# slave_board.net
KiCad netlist of a schematic drawn in EAGLE
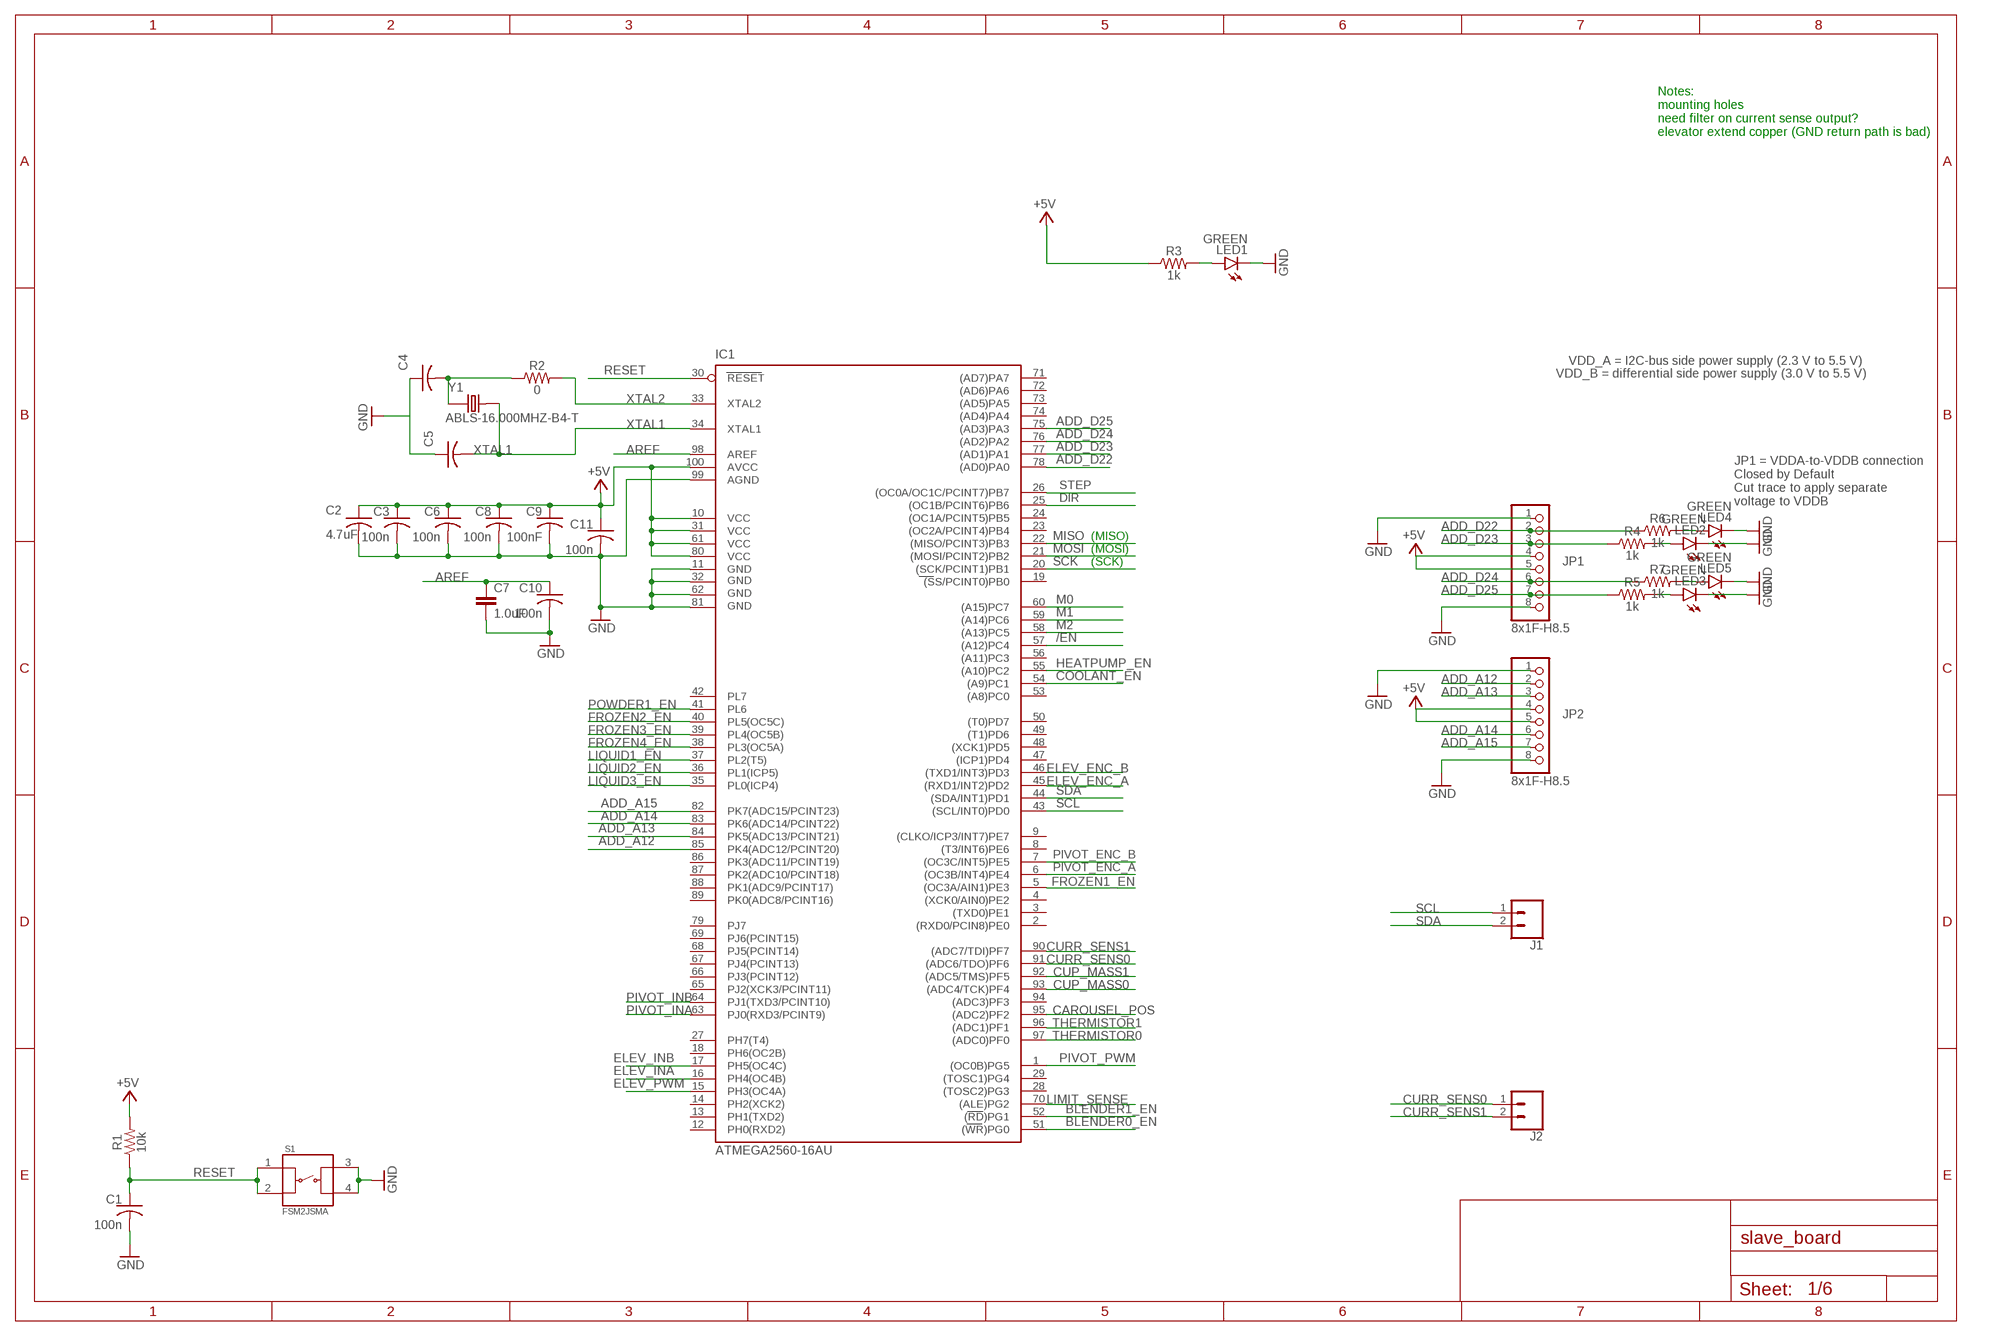
[diagram p0: schematic, sheet 1]
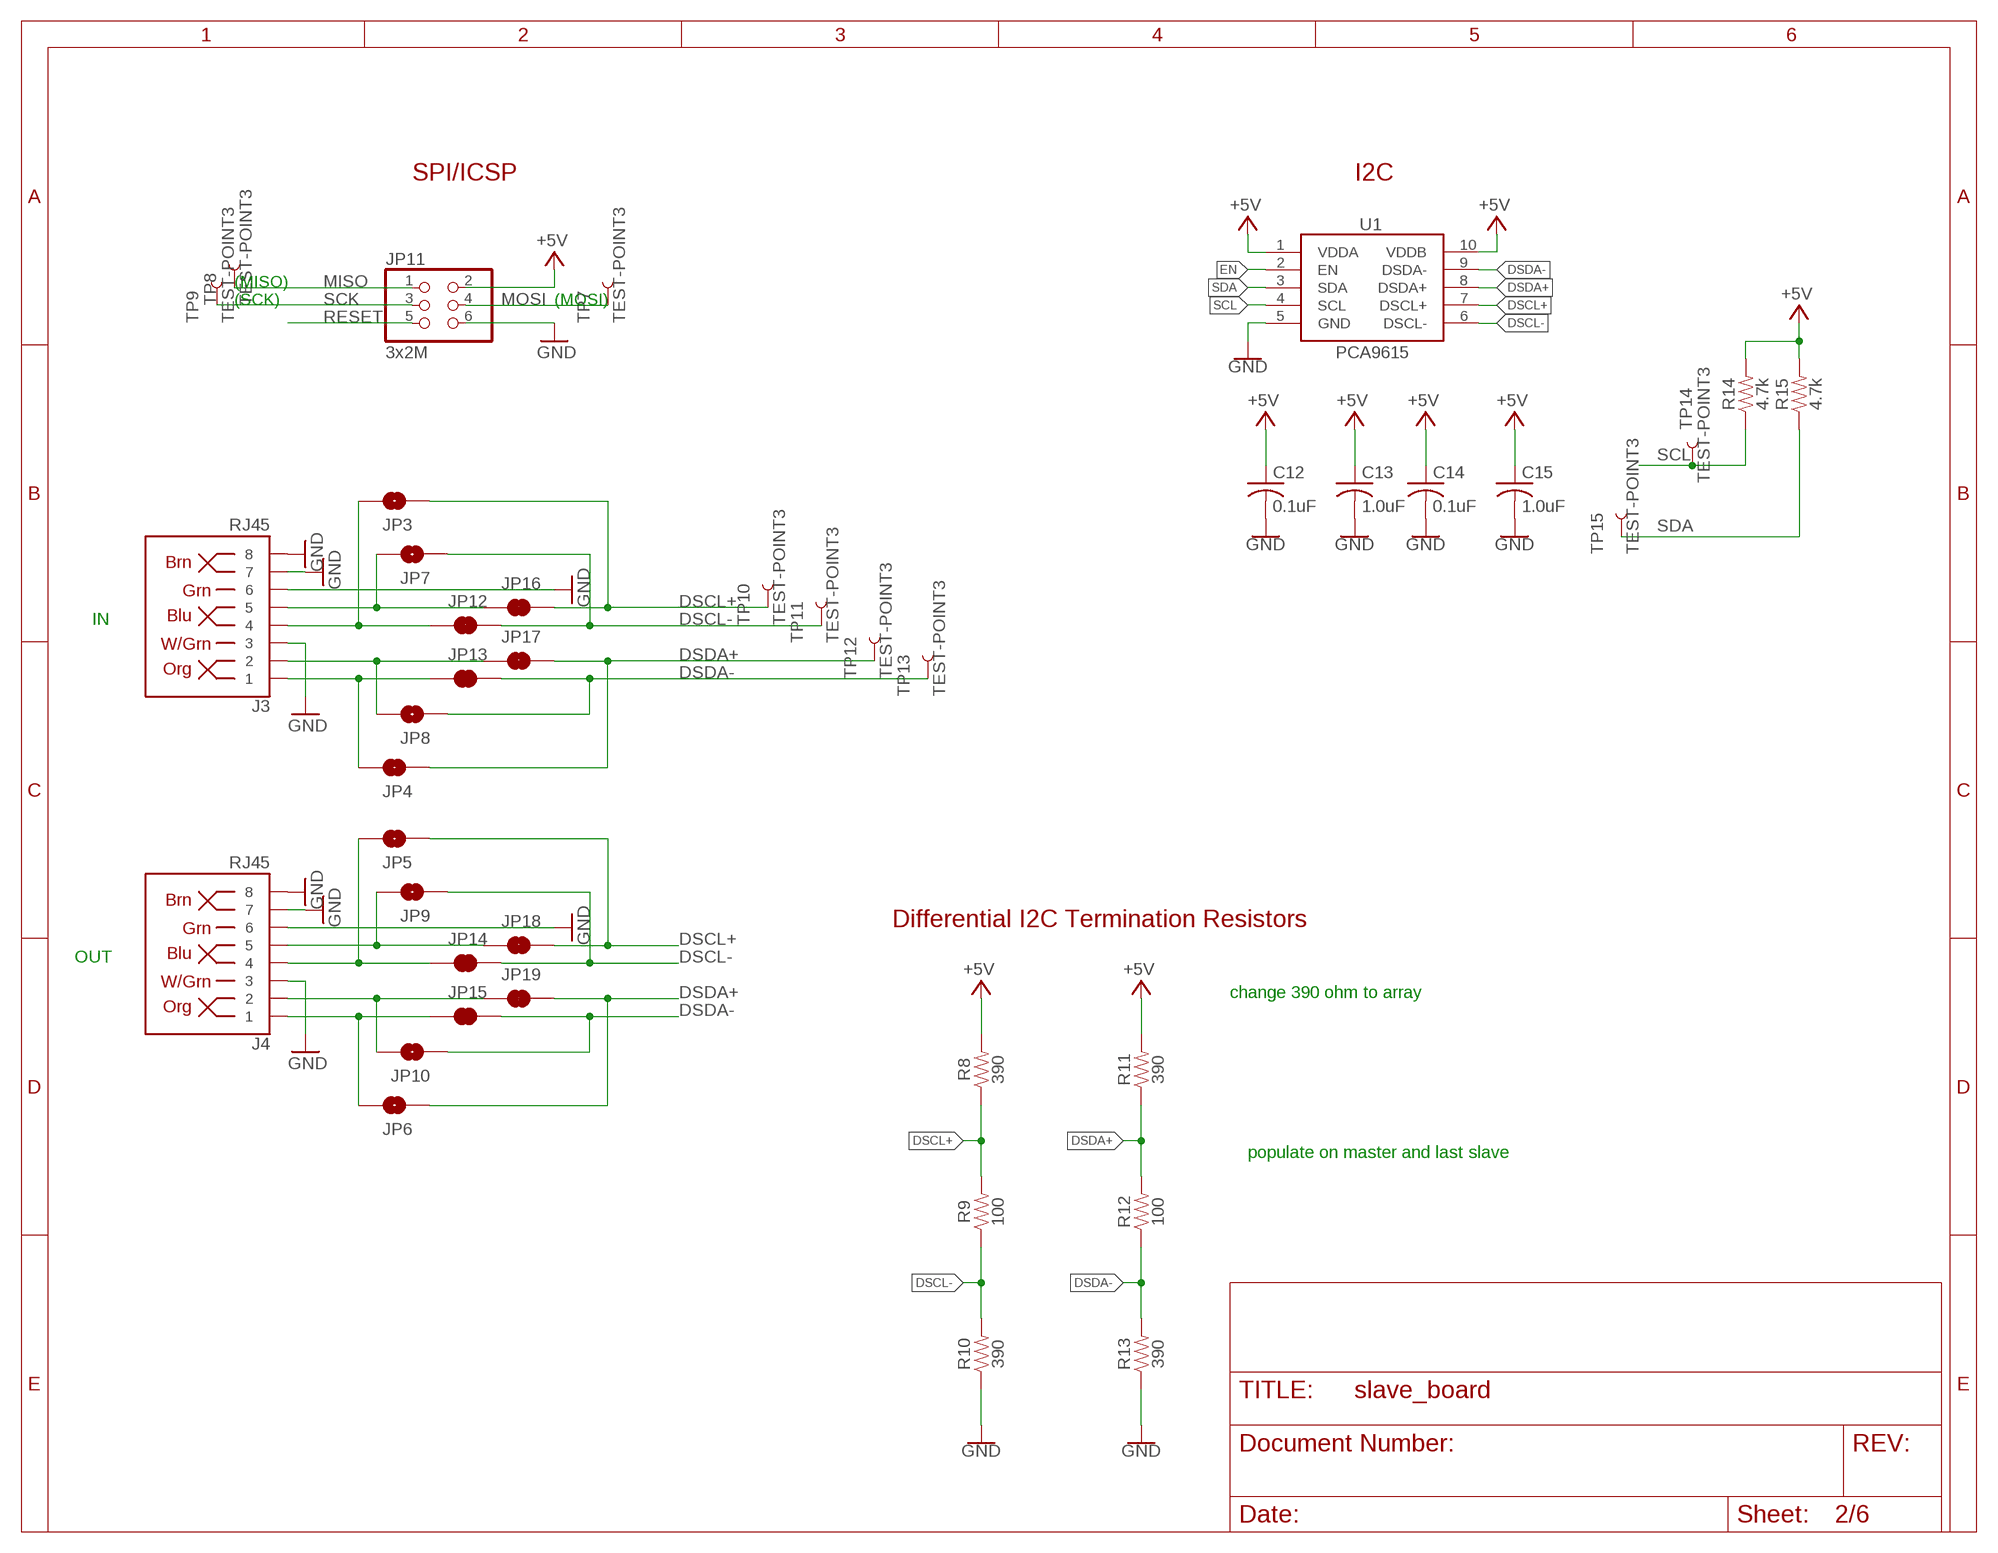
[diagram p1: schematic, sheet 2]
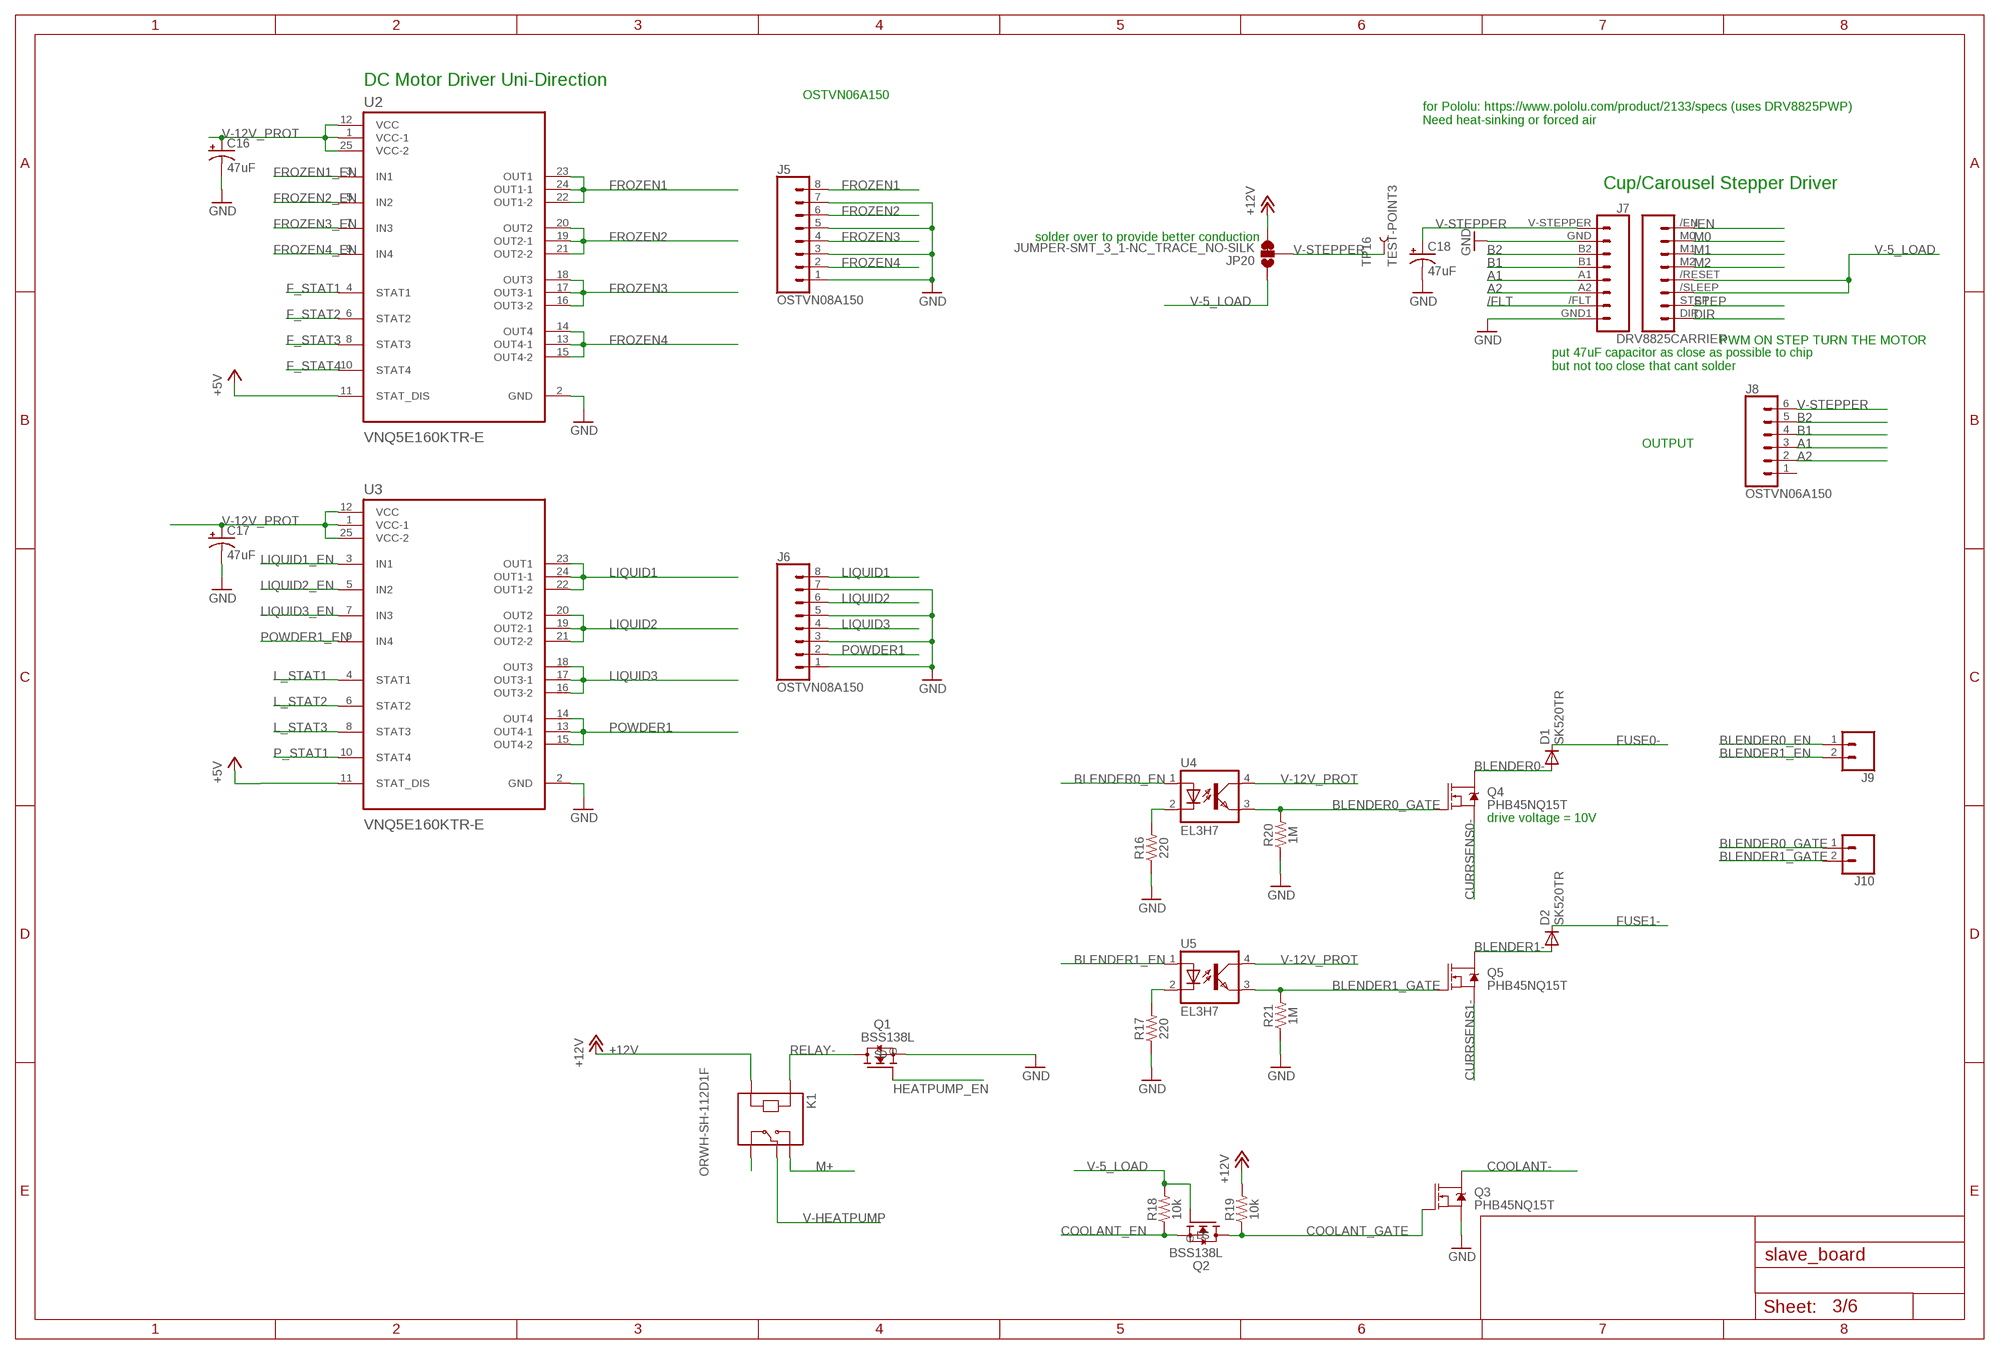
[diagram p2: schematic, sheet 3]
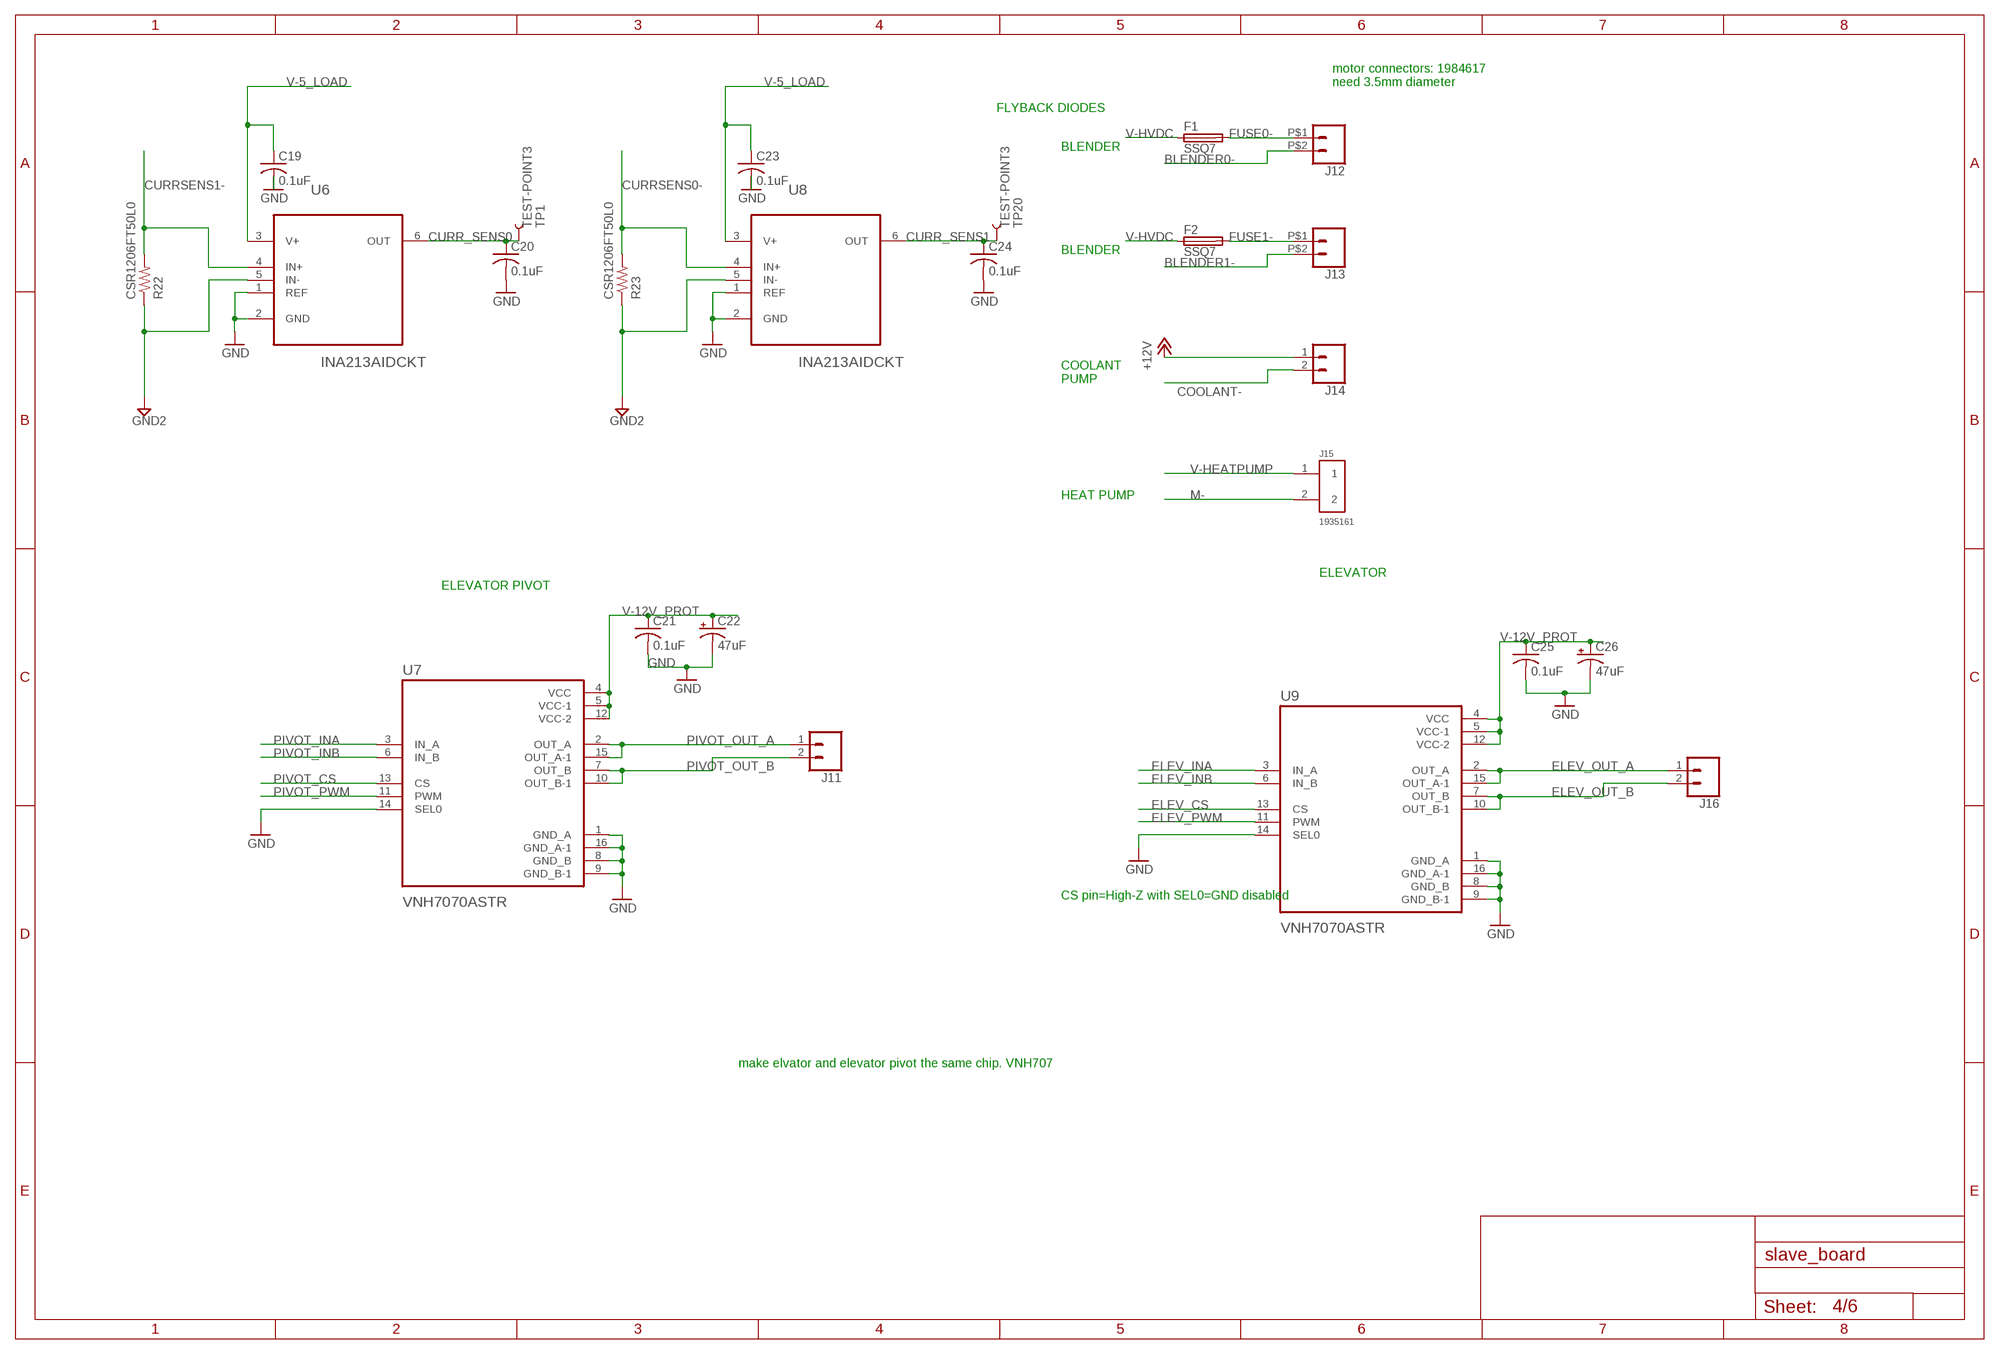
[diagram p3: schematic, sheet 4]
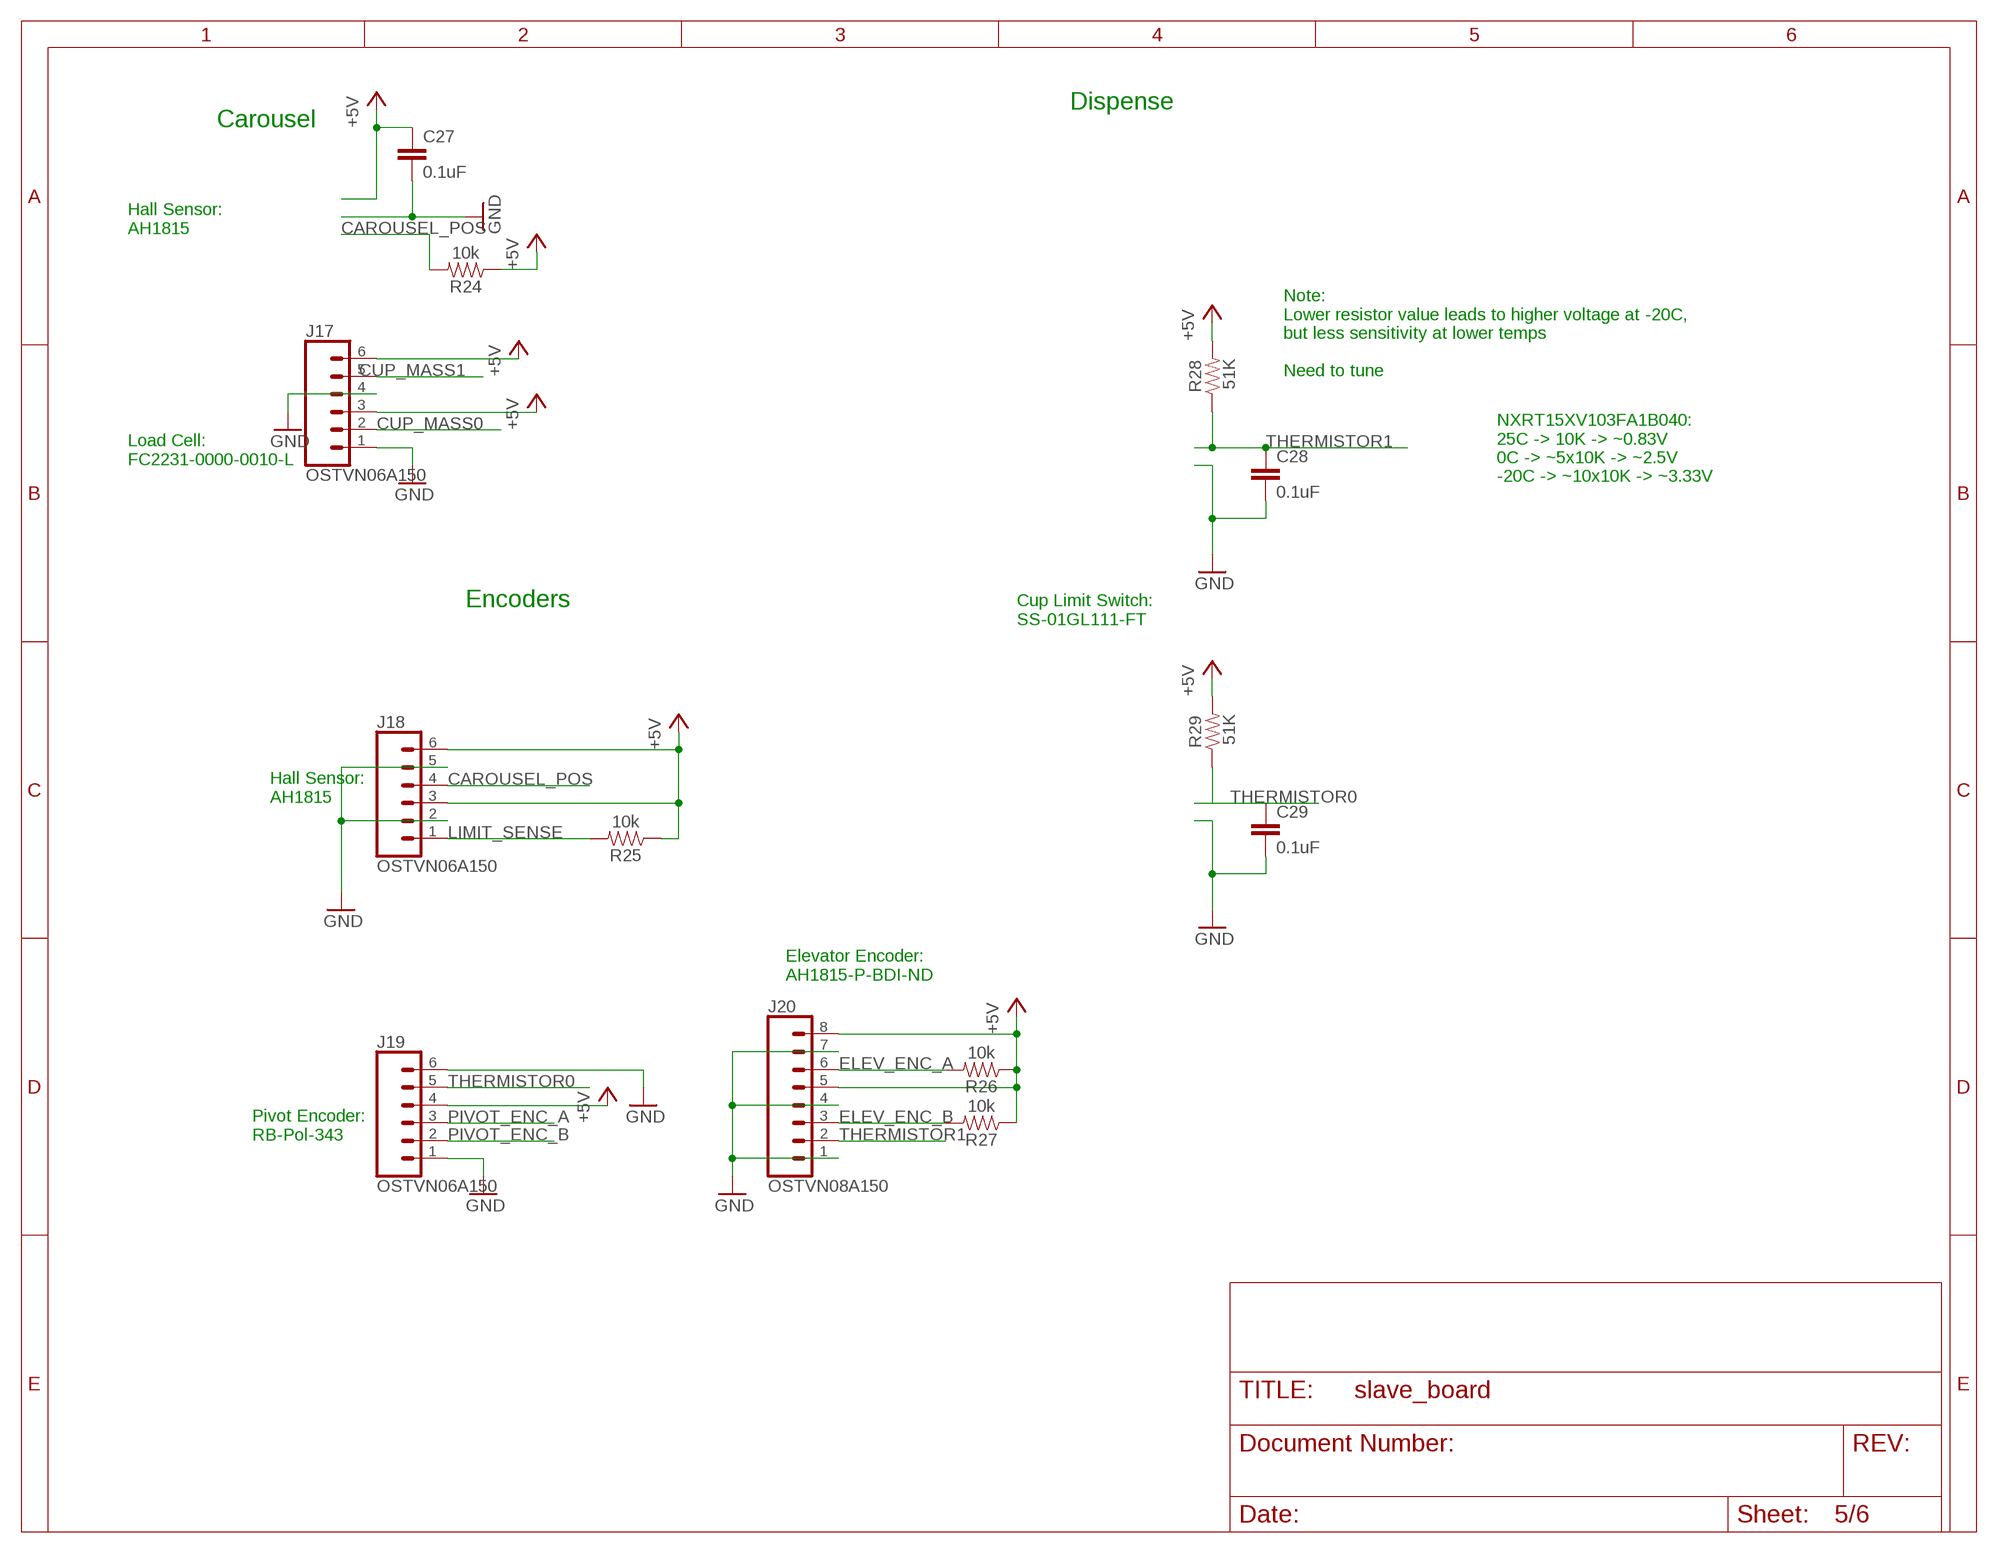
[diagram p4: schematic, sheet 5]
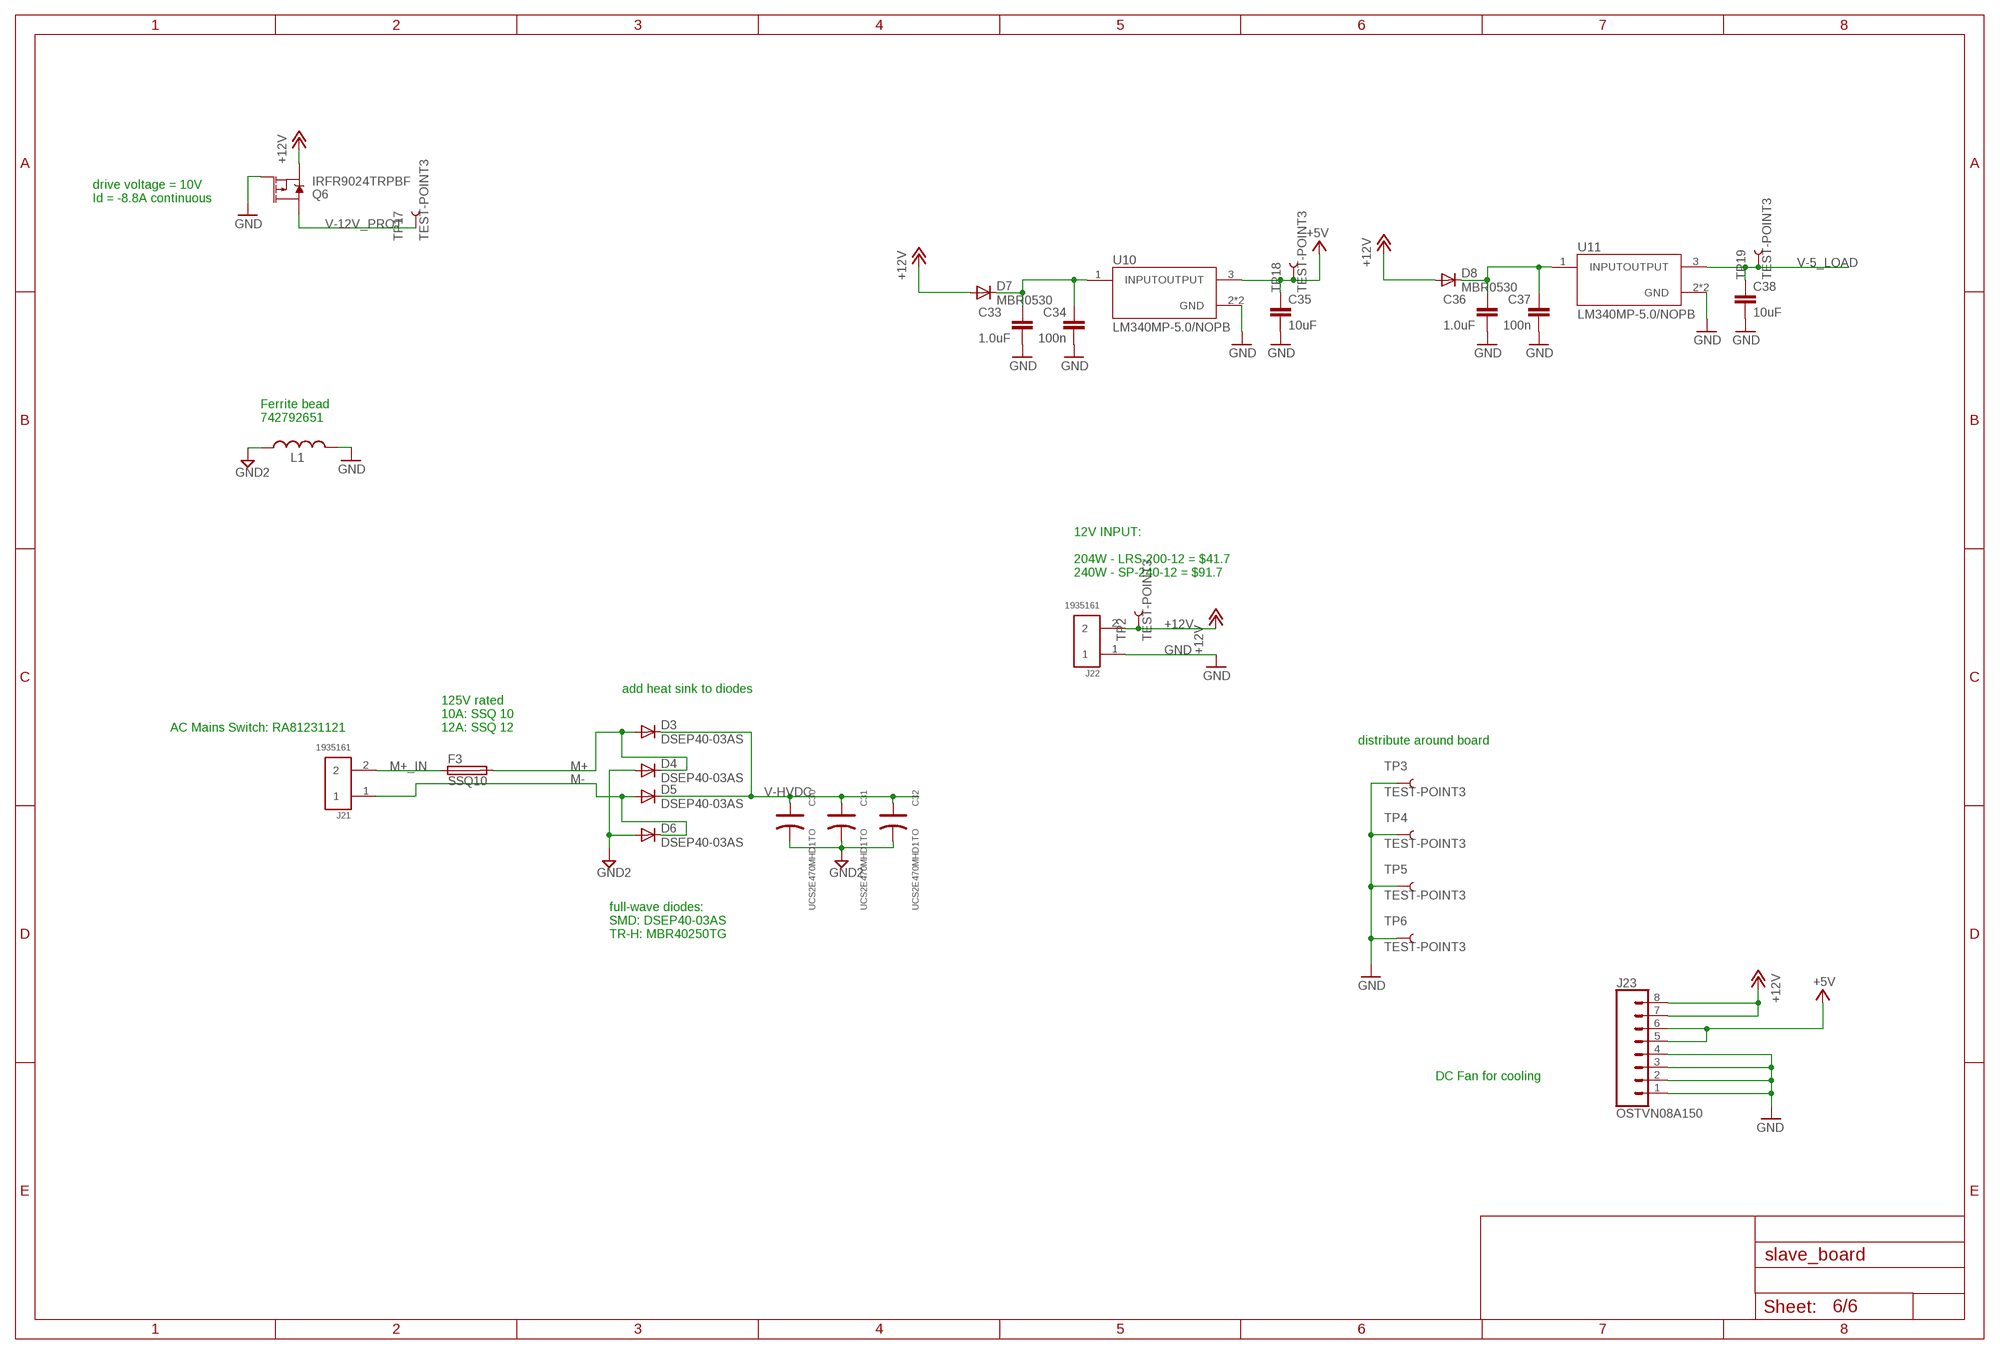
[diagram p5: schematic, sheet 6]

(export (version "E")
  (design (tool "Eeschema 10.0.6"))
  (components
    (comp (ref "C27")
      (value "0.1uF")
      (footprint "eagle-import:0603")
      (libsource (lib "eagle-import") (part "0.1UF-0603-25V-(+80/-20%)"))
    )
    (comp (ref "C28")
      (value "0.1uF")
      (footprint "eagle-import:0603")
      (libsource (lib "eagle-import") (part "0.1UF-0603-25V-(+80/-20%)"))
    )
    (comp (ref "C29")
      (value "0.1uF")
      (footprint "eagle-import:0603")
      (libsource (lib "eagle-import") (part "0.1UF-0603-25V-(+80/-20%)"))
    )
    (comp (ref "J17")
      (value "OSTVN06A150")
      (footprint "eagle-import:6PIN_SCREW_TERMINAL")
      (libsource (lib "eagle-import") (part "OSTVN06A150"))
    )
    (comp (ref "J18")
      (value "OSTVN06A150")
      (footprint "eagle-import:6PIN_SCREW_TERMINAL")
      (libsource (lib "eagle-import") (part "OSTVN06A150"))
    )
    (comp (ref "J19")
      (value "OSTVN06A150")
      (footprint "eagle-import:6PIN_SCREW_TERMINAL")
      (libsource (lib "eagle-import") (part "OSTVN06A150"))
    )
    (comp (ref "J20")
      (value "OSTVN08A150")
      (footprint "eagle-import:8PIN_SCREW_TERMINAL")
      (libsource (lib "eagle-import") (part "OSTVN08A150"))
    )
    (comp (ref "R24")
      (value "10k")
      (footprint "eagle-import:0603")
      (libsource (lib "eagle-import") (part "10KOHM-0603-1/10W-1%"))
    )
    (comp (ref "R25")
      (value "10k")
      (footprint "eagle-import:0603")
      (libsource (lib "eagle-import") (part "10KOHM-0603-1/10W-1%"))
    )
    (comp (ref "R26")
      (value "10k")
      (footprint "eagle-import:0603")
      (libsource (lib "eagle-import") (part "10KOHM-0603-1/10W-1%"))
    )
    (comp (ref "R27")
      (value "10k")
      (footprint "eagle-import:0603")
      (libsource (lib "eagle-import") (part "10KOHM-0603-1/10W-1%"))
    )
    (comp (ref "R28")
      (value "51K")
      (footprint "eagle-import:0603")
      (libsource (lib "eagle-import") (part "RESISTOR0603"))
    )
    (comp (ref "R29")
      (value "51K")
      (footprint "eagle-import:0603")
      (libsource (lib "eagle-import") (part "RESISTOR0603"))
    )
    (comp (ref "C30")
      (value "UCS2E470MHD1TO")
      (footprint "eagle-import:UCS2E470MHD1TO")
      (libsource (lib "eagle-import") (part "UCS2E470MHD1TO"))
    )
    (comp (ref "C31")
      (value "UCS2E470MHD1TO")
      (footprint "eagle-import:UCS2E470MHD1TO")
      (libsource (lib "eagle-import") (part "UCS2E470MHD1TO"))
    )
    (comp (ref "C32")
      (value "UCS2E470MHD1TO")
      (footprint "eagle-import:UCS2E470MHD1TO")
      (libsource (lib "eagle-import") (part "UCS2E470MHD1TO"))
    )
    (comp (ref "C33")
      (value "1.0uF")
      (footprint "eagle-import:0603")
      (libsource (lib "eagle-import") (part "1.0UF-0603-16V-10%"))
    )
    (comp (ref "C34")
      (value "100n")
      (footprint "eagle-import:C0603-ROUND")
      (libsource (lib "eagle-import") (part "C-EU0603-RND"))
    )
    (comp (ref "C35")
      (value "10uF")
      (footprint "eagle-import:0805")
      (libsource (lib "eagle-import") (part "10UF-0805-10V-10%"))
    )
    (comp (ref "C36")
      (value "1.0uF")
      (footprint "eagle-import:0603")
      (libsource (lib "eagle-import") (part "1.0UF-0603-16V-10%"))
    )
    (comp (ref "C37")
      (value "100n")
      (footprint "eagle-import:C0603-ROUND")
      (libsource (lib "eagle-import") (part "C-EU0603-RND"))
    )
    (comp (ref "C38")
      (value "10uF")
      (footprint "eagle-import:0805")
      (libsource (lib "eagle-import") (part "10UF-0805-10V-10%"))
    )
    (comp (ref "D3")
      (value "DSEP40-03AS")
      (footprint "eagle-import:DSEP40-03AS")
      (libsource (lib "eagle-import") (part "DSEP40-03AS"))
    )
    (comp (ref "D4")
      (value "DSEP40-03AS")
      (footprint "eagle-import:DSEP40-03AS")
      (libsource (lib "eagle-import") (part "DSEP40-03AS"))
    )
    (comp (ref "D5")
      (value "DSEP40-03AS")
      (footprint "eagle-import:DSEP40-03AS")
      (libsource (lib "eagle-import") (part "DSEP40-03AS"))
    )
    (comp (ref "D6")
      (value "DSEP40-03AS")
      (footprint "eagle-import:DSEP40-03AS")
      (libsource (lib "eagle-import") (part "DSEP40-03AS"))
    )
    (comp (ref "D7")
      (value "MBR0530")
      (footprint "eagle-import:MBR0530")
      (libsource (lib "eagle-import") (part "MBR0530"))
    )
    (comp (ref "D8")
      (value "MBR0530")
      (footprint "eagle-import:MBR0530")
      (libsource (lib "eagle-import") (part "MBR0530"))
    )
    (comp (ref "F3")
      (value "SSQ10")
      (footprint "eagle-import:SSQ10")
      (libsource (lib "eagle-import") (part "SSQ10"))
    )
    (comp (ref "J21")
      (value "1935161")
      (footprint "eagle-import:PHOENIX_1935161")
      (fields (field (name "MF") "Phoenix Contact"))
      (libsource (lib "eagle-import") (part "1935161"))
    )
    (comp (ref "J22")
      (value "1935161")
      (footprint "eagle-import:PHOENIX_1935161")
      (fields (field (name "MF") "Phoenix Contact"))
      (libsource (lib "eagle-import") (part "1935161"))
    )
    (comp (ref "J23")
      (value "OSTVN08A150")
      (footprint "eagle-import:8PIN_SCREW_TERMINAL")
      (libsource (lib "eagle-import") (part "OSTVN08A150"))
    )
    (comp (ref "L1")
      (value "742792651")
      (footprint "eagle-import:742792651")
      (libsource (lib "eagle-import") (part "742792651"))
    )
    (comp (ref "Q6")
      (value "IRFR9024TRPBF")
      (footprint "eagle-import:IRFR9024TRPBF")
      (libsource (lib "eagle-import") (part "IRFR9024TRPBF"))
    )
    (comp (ref "TP2")
      (value "TEST-POINT3")
      (footprint "eagle-import:PAD.03X.03")
      (libsource (lib "eagle-import") (part "TEST-POINT3"))
    )
    (comp (ref "TP3")
      (value "TEST-POINT3")
      (footprint "eagle-import:PAD.03X.03")
      (libsource (lib "eagle-import") (part "TEST-POINT3"))
    )
    (comp (ref "TP4")
      (value "TEST-POINT3")
      (footprint "eagle-import:PAD.03X.03")
      (libsource (lib "eagle-import") (part "TEST-POINT3"))
    )
    (comp (ref "TP5")
      (value "TEST-POINT3")
      (footprint "eagle-import:PAD.03X.03")
      (libsource (lib "eagle-import") (part "TEST-POINT3"))
    )
    (comp (ref "TP6")
      (value "TEST-POINT3")
      (footprint "eagle-import:PAD.03X.03")
      (libsource (lib "eagle-import") (part "TEST-POINT3"))
    )
    (comp (ref "TP17")
      (value "TEST-POINT3")
      (footprint "eagle-import:PAD.03X.03")
      (libsource (lib "eagle-import") (part "TEST-POINT3"))
    )
    (comp (ref "TP18")
      (value "TEST-POINT3")
      (footprint "eagle-import:PAD.03X.03")
      (libsource (lib "eagle-import") (part "TEST-POINT3"))
    )
    (comp (ref "TP19")
      (value "TEST-POINT3")
      (footprint "eagle-import:PAD.03X.03")
      (libsource (lib "eagle-import") (part "TEST-POINT3"))
    )
    (comp (ref "U10")
      (value "LM340MP-5.0/NOPB")
      (footprint "eagle-import:SOT230P700X180-4N")
      (fields
        (field (name "DIGI-KEY_PART_NUMBER") "296-35905-1-ND")
        (field (name "MF") "Texas Instruments")
        (field (name "MP") "LM340MP-5.0")
      )
      (libsource (lib "eagle-import") (part "LM340MP-5.0/NOPB"))
    )
    (comp (ref "U11")
      (value "LM340MP-5.0/NOPB")
      (footprint "eagle-import:SOT230P700X180-4N")
      (fields
        (field (name "DIGI-KEY_PART_NUMBER") "296-35905-1-ND")
        (field (name "MF") "Texas Instruments")
        (field (name "MP") "LM340MP-5.0")
      )
      (libsource (lib "eagle-import") (part "LM340MP-5.0/NOPB"))
    )
    (comp (ref "C19")
      (value "0.1uF")
      (footprint "eagle-import:C0603")
      (libsource (lib "eagle-import") (part "C-USC0603"))
    )
    (comp (ref "C20")
      (value "0.1uF")
      (footprint "eagle-import:C0603")
      (libsource (lib "eagle-import") (part "C-USC0603"))
    )
    (comp (ref "C21")
      (value "0.1uF")
      (footprint "eagle-import:C0603")
      (libsource (lib "eagle-import") (part "C-USC0603"))
    )
    (comp (ref "C22")
      (value "47uF")
      (footprint "eagle-import:PANASONIC_D")
      (libsource (lib "eagle-import") (part "47UF-POLAR-PANASONIC_D-35V-20%"))
    )
    (comp (ref "C23")
      (value "0.1uF")
      (footprint "eagle-import:C0603")
      (libsource (lib "eagle-import") (part "C-USC0603"))
    )
    (comp (ref "C24")
      (value "0.1uF")
      (footprint "eagle-import:C0603")
      (libsource (lib "eagle-import") (part "C-USC0603"))
    )
    (comp (ref "C25")
      (value "0.1uF")
      (footprint "eagle-import:C0603")
      (libsource (lib "eagle-import") (part "C-USC0603"))
    )
    (comp (ref "C26")
      (value "47uF")
      (footprint "eagle-import:PANASONIC_D")
      (libsource (lib "eagle-import") (part "47UF-POLAR-PANASONIC_D-35V-20%"))
    )
    (comp (ref "F1")
      (value "SSQ7")
      (footprint "eagle-import:SSQ7")
      (libsource (lib "eagle-import") (part "SSQ7"))
    )
    (comp (ref "F2")
      (value "SSQ7")
      (footprint "eagle-import:SSQ7")
      (libsource (lib "eagle-import") (part "SSQ7"))
    )
    (comp (ref "J11")
      (value "CONN_02")
      (footprint "eagle-import:1X02")
      (libsource (lib "eagle-import") (part "CONN_02"))
    )
    (comp (ref "J12")
      (value "CONN_02PTH2")
      (footprint "eagle-import:1X02_BIG")
      (libsource (lib "eagle-import") (part "CONN_02PTH2"))
    )
    (comp (ref "J13")
      (value "CONN_02PTH2")
      (footprint "eagle-import:1X02_BIG")
      (libsource (lib "eagle-import") (part "CONN_02PTH2"))
    )
    (comp (ref "J14")
      (value "CONN_02")
      (footprint "eagle-import:1X02")
      (libsource (lib "eagle-import") (part "CONN_02"))
    )
    (comp (ref "J15")
      (value "1935161")
      (footprint "eagle-import:PHOENIX_1935161")
      (fields (field (name "MF") "Phoenix Contact"))
      (libsource (lib "eagle-import") (part "1935161"))
    )
    (comp (ref "J16")
      (value "CONN_02")
      (footprint "eagle-import:1X02")
      (libsource (lib "eagle-import") (part "CONN_02"))
    )
    (comp (ref "R22")
      (value "CSR1206FT50L0")
      (footprint "eagle-import:CSR1206FT50L0")
      (libsource (lib "eagle-import") (part "CSR1206FT50L0"))
    )
    (comp (ref "R23")
      (value "CSR1206FT50L0")
      (footprint "eagle-import:CSR1206FT50L0")
      (libsource (lib "eagle-import") (part "CSR1206FT50L0"))
    )
    (comp (ref "TP1")
      (value "TEST-POINT3")
      (footprint "eagle-import:PAD.03X.03")
      (libsource (lib "eagle-import") (part "TEST-POINT3"))
    )
    (comp (ref "TP20")
      (value "TEST-POINT3")
      (footprint "eagle-import:PAD.03X.03")
      (libsource (lib "eagle-import") (part "TEST-POINT3"))
    )
    (comp (ref "U6")
      (value "INA213AIDCKT")
      (footprint "eagle-import:SOT65P210X110-6N")
      (fields (field (name "MF") "Texas Instruments"))
      (libsource (lib "eagle-import") (part "INA213AIDCKT"))
    )
    (comp (ref "U7")
      (value "VNH7070ASTR")
      (footprint "eagle-import:VNH7070ASTR")
      (fields (field (name "MF") "STMicroelectronics"))
      (libsource (lib "eagle-import") (part "VNH7070ASTR"))
    )
    (comp (ref "U8")
      (value "INA213AIDCKT")
      (footprint "eagle-import:SOT65P210X110-6N")
      (fields (field (name "MF") "Texas Instruments"))
      (libsource (lib "eagle-import") (part "INA213AIDCKT"))
    )
    (comp (ref "U9")
      (value "VNH7070ASTR")
      (footprint "eagle-import:VNH7070ASTR")
      (fields (field (name "MF") "STMicroelectronics"))
      (libsource (lib "eagle-import") (part "VNH7070ASTR"))
    )
    (comp (ref "C12")
      (value "0.1uF")
      (footprint "eagle-import:C0603")
      (libsource (lib "eagle-import") (part "C-USC0603"))
    )
    (comp (ref "C13")
      (value "1.0uF")
      (footprint "eagle-import:C0603")
      (libsource (lib "eagle-import") (part "C-USC0603"))
    )
    (comp (ref "C14")
      (value "0.1uF")
      (footprint "eagle-import:C0603")
      (libsource (lib "eagle-import") (part "C-USC0603"))
    )
    (comp (ref "C15")
      (value "1.0uF")
      (footprint "eagle-import:C0603")
      (libsource (lib "eagle-import") (part "C-USC0603"))
    )
    (comp (ref "J3")
      (value "RJ45")
      (footprint "eagle-import:RJ45-8")
      (libsource (lib "eagle-import") (part "RJ45-8"))
    )
    (comp (ref "J4")
      (value "RJ45")
      (footprint "eagle-import:RJ45-8")
      (libsource (lib "eagle-import") (part "RJ45-8"))
    )
    (comp (ref "JP3")
      (value "JUMPER-SMT_2_NO_NO-SILK")
      (footprint "eagle-import:SMT-JUMPER_2_NO_NO-SILK")
      (libsource (lib "eagle-import") (part "JUMPER-SMT_2_NO_NO-SILK"))
    )
    (comp (ref "JP4")
      (value "JUMPER-SMT_2_NO_NO-SILK")
      (footprint "eagle-import:SMT-JUMPER_2_NO_NO-SILK")
      (libsource (lib "eagle-import") (part "JUMPER-SMT_2_NO_NO-SILK"))
    )
    (comp (ref "JP5")
      (value "JUMPER-SMT_2_NO_NO-SILK")
      (footprint "eagle-import:SMT-JUMPER_2_NO_NO-SILK")
      (libsource (lib "eagle-import") (part "JUMPER-SMT_2_NO_NO-SILK"))
    )
    (comp (ref "JP6")
      (value "JUMPER-SMT_2_NO_NO-SILK")
      (footprint "eagle-import:SMT-JUMPER_2_NO_NO-SILK")
      (libsource (lib "eagle-import") (part "JUMPER-SMT_2_NO_NO-SILK"))
    )
    (comp (ref "JP7")
      (value "JUMPER-SMT_2_NO_NO-SILK")
      (footprint "eagle-import:SMT-JUMPER_2_NO_NO-SILK")
      (libsource (lib "eagle-import") (part "JUMPER-SMT_2_NO_NO-SILK"))
    )
    (comp (ref "JP8")
      (value "JUMPER-SMT_2_NO_NO-SILK")
      (footprint "eagle-import:SMT-JUMPER_2_NO_NO-SILK")
      (libsource (lib "eagle-import") (part "JUMPER-SMT_2_NO_NO-SILK"))
    )
    (comp (ref "JP9")
      (value "JUMPER-SMT_2_NO_NO-SILK")
      (footprint "eagle-import:SMT-JUMPER_2_NO_NO-SILK")
      (libsource (lib "eagle-import") (part "JUMPER-SMT_2_NO_NO-SILK"))
    )
    (comp (ref "JP10")
      (value "JUMPER-SMT_2_NO_NO-SILK")
      (footprint "eagle-import:SMT-JUMPER_2_NO_NO-SILK")
      (libsource (lib "eagle-import") (part "JUMPER-SMT_2_NO_NO-SILK"))
    )
    (comp (ref "JP11")
      (value "3x2M")
      (footprint "eagle-import:2X03")
      (libsource (lib "eagle-import") (part "PINHD-2X3"))
    )
    (comp (ref "JP12")
      (value "JUMPER-SMT_2_NC_TRACE_NO-SILK")
      (footprint "eagle-import:SMT-JUMPER_2_NC_TRACE_NO-SILK")
      (libsource (lib "eagle-import") (part "JUMPER-SMT_2_NC_TRACE_NO-SILK"))
    )
    (comp (ref "JP13")
      (value "JUMPER-SMT_2_NC_TRACE_NO-SILK")
      (footprint "eagle-import:SMT-JUMPER_2_NC_TRACE_NO-SILK")
      (libsource (lib "eagle-import") (part "JUMPER-SMT_2_NC_TRACE_NO-SILK"))
    )
    (comp (ref "JP14")
      (value "JUMPER-SMT_2_NC_TRACE_NO-SILK")
      (footprint "eagle-import:SMT-JUMPER_2_NC_TRACE_NO-SILK")
      (libsource (lib "eagle-import") (part "JUMPER-SMT_2_NC_TRACE_NO-SILK"))
    )
    (comp (ref "JP15")
      (value "JUMPER-SMT_2_NC_TRACE_NO-SILK")
      (footprint "eagle-import:SMT-JUMPER_2_NC_TRACE_NO-SILK")
      (libsource (lib "eagle-import") (part "JUMPER-SMT_2_NC_TRACE_NO-SILK"))
    )
    (comp (ref "JP16")
      (value "JUMPER-SMT_2_NC_TRACE_NO-SILK")
      (footprint "eagle-import:SMT-JUMPER_2_NC_TRACE_NO-SILK")
      (libsource (lib "eagle-import") (part "JUMPER-SMT_2_NC_TRACE_NO-SILK"))
    )
    (comp (ref "JP17")
      (value "JUMPER-SMT_2_NC_TRACE_NO-SILK")
      (footprint "eagle-import:SMT-JUMPER_2_NC_TRACE_NO-SILK")
      (libsource (lib "eagle-import") (part "JUMPER-SMT_2_NC_TRACE_NO-SILK"))
    )
    (comp (ref "JP18")
      (value "JUMPER-SMT_2_NC_TRACE_NO-SILK")
      (footprint "eagle-import:SMT-JUMPER_2_NC_TRACE_NO-SILK")
      (libsource (lib "eagle-import") (part "JUMPER-SMT_2_NC_TRACE_NO-SILK"))
    )
    (comp (ref "JP19")
      (value "JUMPER-SMT_2_NC_TRACE_NO-SILK")
      (footprint "eagle-import:SMT-JUMPER_2_NC_TRACE_NO-SILK")
      (libsource (lib "eagle-import") (part "JUMPER-SMT_2_NC_TRACE_NO-SILK"))
    )
    (comp (ref "R8")
      (value "390")
      (footprint "eagle-import:0603")
      (libsource (lib "eagle-import") (part "390OHM-0603-1/10W-1%"))
    )
    (comp (ref "R9")
      (value "100")
      (footprint "eagle-import:0603")
      (libsource (lib "eagle-import") (part "100OHM-0603-1/10W-1%"))
    )
    (comp (ref "R10")
      (value "390")
      (footprint "eagle-import:0603")
      (libsource (lib "eagle-import") (part "390OHM-0603-1/10W-1%"))
    )
    (comp (ref "R11")
      (value "390")
      (footprint "eagle-import:0603")
      (libsource (lib "eagle-import") (part "390OHM-0603-1/10W-1%"))
    )
    (comp (ref "R12")
      (value "100")
      (footprint "eagle-import:0603")
      (libsource (lib "eagle-import") (part "100OHM-0603-1/10W-1%"))
    )
    (comp (ref "R13")
      (value "390")
      (footprint "eagle-import:0603")
      (libsource (lib "eagle-import") (part "390OHM-0603-1/10W-1%"))
    )
    (comp (ref "R14")
      (value "4.7k")
      (footprint "eagle-import:0603")
      (libsource (lib "eagle-import") (part "4.7KOHM-0603-1/10W-1%"))
    )
    (comp (ref "R15")
      (value "4.7k")
      (footprint "eagle-import:0603")
      (libsource (lib "eagle-import") (part "4.7KOHM-0603-1/10W-1%"))
    )
    (comp (ref "TP7")
      (value "TEST-POINT3")
      (footprint "eagle-import:PAD.03X.03")
      (libsource (lib "eagle-import") (part "TEST-POINT3"))
    )
    (comp (ref "TP8")
      (value "TEST-POINT3")
      (footprint "eagle-import:PAD.03X.03")
      (libsource (lib "eagle-import") (part "TEST-POINT3"))
    )
    (comp (ref "TP9")
      (value "TEST-POINT3")
      (footprint "eagle-import:PAD.03X.03")
      (libsource (lib "eagle-import") (part "TEST-POINT3"))
    )
    (comp (ref "TP10")
      (value "TEST-POINT3")
      (footprint "eagle-import:PAD.03X.03")
      (libsource (lib "eagle-import") (part "TEST-POINT3"))
    )
    (comp (ref "TP11")
      (value "TEST-POINT3")
      (footprint "eagle-import:PAD.03X.03")
      (libsource (lib "eagle-import") (part "TEST-POINT3"))
    )
    (comp (ref "TP12")
      (value "TEST-POINT3")
      (footprint "eagle-import:PAD.03X.03")
      (libsource (lib "eagle-import") (part "TEST-POINT3"))
    )
    (comp (ref "TP13")
      (value "TEST-POINT3")
      (footprint "eagle-import:PAD.03X.03")
      (libsource (lib "eagle-import") (part "TEST-POINT3"))
    )
    (comp (ref "TP14")
      (value "TEST-POINT3")
      (footprint "eagle-import:PAD.03X.03")
      (libsource (lib "eagle-import") (part "TEST-POINT3"))
    )
    (comp (ref "TP15")
      (value "TEST-POINT3")
      (footprint "eagle-import:PAD.03X.03")
      (libsource (lib "eagle-import") (part "TEST-POINT3"))
    )
    (comp (ref "U1")
      (value "PCA9615")
      (footprint "eagle-import:SPARKFUN-IC-COMMS_TSSOP10")
      (libsource (lib "eagle-import") (part "PCA9615"))
    )
    (comp (ref "C16")
      (value "47uF")
      (footprint "eagle-import:PANASONIC_D")
      (libsource (lib "eagle-import") (part "47UF-POLAR-PANASONIC_D-35V-20%"))
    )
    (comp (ref "C17")
      (value "47uF")
      (footprint "eagle-import:PANASONIC_D")
      (libsource (lib "eagle-import") (part "47UF-POLAR-PANASONIC_D-35V-20%"))
    )
    (comp (ref "C18")
      (value "47uF")
      (footprint "eagle-import:PANASONIC_D")
      (libsource (lib "eagle-import") (part "47UF-POLAR-PANASONIC_D-35V-20%"))
    )
    (comp (ref "D1")
      (value "SK520TR")
      (footprint "eagle-import:SK520TR")
      (libsource (lib "eagle-import") (part "SK520TR"))
    )
    (comp (ref "D2")
      (value "SK520TR")
      (footprint "eagle-import:SK520TR")
      (libsource (lib "eagle-import") (part "SK520TR"))
    )
    (comp (ref "J5")
      (value "OSTVN08A150")
      (footprint "eagle-import:8PIN_SCREW_TERMINAL")
      (libsource (lib "eagle-import") (part "OSTVN08A150"))
    )
    (comp (ref "J6")
      (value "OSTVN08A150")
      (footprint "eagle-import:8PIN_SCREW_TERMINAL")
      (libsource (lib "eagle-import") (part "OSTVN08A150"))
    )
    (comp (ref "J7")
      (value "DRV8825CARRIER")
      (footprint "eagle-import:DRV8825CARRIER")
      (libsource (lib "eagle-import") (part "DRV8825CARRIER"))
    )
    (comp (ref "J8")
      (value "OSTVN06A150")
      (footprint "eagle-import:6PIN_SCREW_TERMINAL")
      (libsource (lib "eagle-import") (part "OSTVN06A150"))
    )
    (comp (ref "J9")
      (value "CONN_02")
      (footprint "eagle-import:1X02")
      (libsource (lib "eagle-import") (part "CONN_02"))
    )
    (comp (ref "J10")
      (value "CONN_02")
      (footprint "eagle-import:1X02")
      (libsource (lib "eagle-import") (part "CONN_02"))
    )
    (comp (ref "JP20")
      (value "JUMPER-SMT_3_1-NC_TRACE_NO-SILK")
      (footprint "eagle-import:SMT-JUMPER_3_1-NC_TRACE_NO-SILK")
      (libsource (lib "eagle-import") (part "JUMPER-SMT_3_1-NC_TRACE_NO-SILK"))
    )
    (comp (ref "K1")
      (value "ORWH-SH-112D1F")
      (footprint "eagle-import:ORWH-SH-112D1F")
      (fields (field (name "MF") "TE Connectivity") (field (name "MP") "1-1721150-3"))
      (libsource (lib "eagle-import") (part "ORWH-SH-112D1F"))
    )
    (comp (ref "Q1")
      (value "BSS138L")
      (footprint "eagle-import:BSS138L")
      (fields (field (name "MF") "ON Semiconductor"))
      (libsource (lib "eagle-import") (part "BSS138L"))
    )
    (comp (ref "Q2")
      (value "BSS138L")
      (footprint "eagle-import:BSS138L")
      (fields (field (name "MF") "ON Semiconductor"))
      (libsource (lib "eagle-import") (part "BSS138L"))
    )
    (comp (ref "Q3")
      (value "PHB45NQ15T")
      (footprint "eagle-import:PHB45NQ15T")
      (libsource (lib "eagle-import") (part "PHB45NQ15T"))
    )
    (comp (ref "Q4")
      (value "PHB45NQ15T")
      (footprint "eagle-import:PHB45NQ15T")
      (libsource (lib "eagle-import") (part "PHB45NQ15T"))
    )
    (comp (ref "Q5")
      (value "PHB45NQ15T")
      (footprint "eagle-import:PHB45NQ15T")
      (libsource (lib "eagle-import") (part "PHB45NQ15T"))
    )
    (comp (ref "R16")
      (value "220")
      (footprint "eagle-import:0603")
      (libsource (lib "eagle-import") (part "220OHM-0603-1/10W-1%"))
    )
    (comp (ref "R17")
      (value "220")
      (footprint "eagle-import:0603")
      (libsource (lib "eagle-import") (part "220OHM-0603-1/10W-1%"))
    )
    (comp (ref "R18")
      (value "10k")
      (footprint "eagle-import:0603")
      (libsource (lib "eagle-import") (part "10KOHM-0603-1/10W-1%"))
    )
    (comp (ref "R19")
      (value "10k")
      (footprint "eagle-import:0603")
      (libsource (lib "eagle-import") (part "10KOHM-0603-1/10W-1%"))
    )
    (comp (ref "R20")
      (value "1M")
      (footprint "eagle-import:0603")
      (libsource (lib "eagle-import") (part "1MOHM-0603-1/4W-5%"))
    )
    (comp (ref "R21")
      (value "1M")
      (footprint "eagle-import:0603")
      (libsource (lib "eagle-import") (part "1MOHM-0603-1/4W-5%"))
    )
    (comp (ref "TP16")
      (value "TEST-POINT3")
      (footprint "eagle-import:PAD.03X.03")
      (libsource (lib "eagle-import") (part "TEST-POINT3"))
    )
    (comp (ref "U2")
      (value "VNQ5E160KTR-E")
      (footprint "eagle-import:SOP80P1030X245-25N")
      (fields (field (name "MF") "STMicroelectronics"))
      (libsource (lib "eagle-import") (part "VNQ5E160KTR-E"))
    )
    (comp (ref "U3")
      (value "VNQ5E160KTR-E")
      (footprint "eagle-import:SOP80P1030X245-25N")
      (fields (field (name "MF") "STMicroelectronics"))
      (libsource (lib "eagle-import") (part "VNQ5E160KTR-E"))
    )
    (comp (ref "U4")
      (value "EL3H7")
      (footprint "eagle-import:EL3H7")
      (libsource (lib "eagle-import") (part "EL3H7"))
    )
    (comp (ref "U5")
      (value "EL3H7")
      (footprint "eagle-import:EL3H7")
      (libsource (lib "eagle-import") (part "EL3H7"))
    )
    (comp (ref "C1")
      (value "100n")
      (footprint "eagle-import:C0603")
      (libsource (lib "eagle-import") (part "C-USC0603"))
    )
    (comp (ref "C2")
      (value "4.7uF")
      (footprint "eagle-import:C0603")
      (libsource (lib "eagle-import") (part "C-USC0603"))
    )
    (comp (ref "C3")
      (value "100n")
      (footprint "eagle-import:C0603")
      (libsource (lib "eagle-import") (part "C-USC0603"))
    )
    (comp (ref "C4")
      (value "15pF")
      (footprint "eagle-import:C0603")
      (libsource (lib "eagle-import") (part "C-USC0603"))
    )
    (comp (ref "C5")
      (value "15pF")
      (footprint "eagle-import:C0603")
      (libsource (lib "eagle-import") (part "C-USC0603"))
    )
    (comp (ref "C6")
      (value "100n")
      (footprint "eagle-import:C0603")
      (libsource (lib "eagle-import") (part "C-USC0603"))
    )
    (comp (ref "C7")
      (value "1.0uF")
      (footprint "eagle-import:0603")
      (libsource (lib "eagle-import") (part "1.0UF-0603-16V-10%"))
    )
    (comp (ref "C8")
      (value "100n")
      (footprint "eagle-import:C0603")
      (libsource (lib "eagle-import") (part "C-USC0603"))
    )
    (comp (ref "C9")
      (value "100nF")
      (footprint "eagle-import:C0603")
      (libsource (lib "eagle-import") (part "C-USC0603"))
    )
    (comp (ref "C10")
      (value "100n")
      (footprint "eagle-import:C0603")
      (libsource (lib "eagle-import") (part "C-USC0603"))
    )
    (comp (ref "C11")
      (value "100n")
      (footprint "eagle-import:C0603")
      (libsource (lib "eagle-import") (part "C-USC0603"))
    )
    (comp (ref "IC1")
      (value "ATMEGA2560-16AU")
      (footprint "eagle-import:TQFP100")
      (libsource (lib "eagle-import") (part "ATMEGA2560AU2560-16"))
    )
    (comp (ref "J1")
      (value "CONN_02")
      (footprint "eagle-import:1X02")
      (libsource (lib "eagle-import") (part "CONN_02"))
    )
    (comp (ref "J2")
      (value "CONN_02")
      (footprint "eagle-import:1X02")
      (libsource (lib "eagle-import") (part "CONN_02"))
    )
    (comp (ref "JP1")
      (value "8x1F-H8.5")
      (footprint "eagle-import:1X08")
      (libsource (lib "eagle-import") (part "PINHD-1X8"))
    )
    (comp (ref "JP2")
      (value "8x1F-H8.5")
      (footprint "eagle-import:1X08")
      (libsource (lib "eagle-import") (part "PINHD-1X8"))
    )
    (comp (ref "LED1")
      (value "GREEN")
      (footprint "eagle-import:CHIP-LED0805")
      (libsource (lib "eagle-import") (part "LEDCHIP-LED0805"))
    )
    (comp (ref "LED2")
      (value "GREEN")
      (footprint "eagle-import:CHIP-LED0805")
      (libsource (lib "eagle-import") (part "LEDCHIP-LED0805"))
    )
    (comp (ref "LED3")
      (value "GREEN")
      (footprint "eagle-import:CHIP-LED0805")
      (libsource (lib "eagle-import") (part "LEDCHIP-LED0805"))
    )
    (comp (ref "LED4")
      (value "GREEN")
      (footprint "eagle-import:CHIP-LED0805")
      (libsource (lib "eagle-import") (part "LEDCHIP-LED0805"))
    )
    (comp (ref "LED5")
      (value "GREEN")
      (footprint "eagle-import:CHIP-LED0805")
      (libsource (lib "eagle-import") (part "LEDCHIP-LED0805"))
    )
    (comp (ref "R1")
      (value "10k")
      (footprint "eagle-import:0603")
      (libsource (lib "eagle-import") (part "10KOHM-0603-1/10W-1%"))
    )
    (comp (ref "R2")
      (value "0")
      (footprint "eagle-import:0603")
      (libsource (lib "eagle-import") (part "0OHM-0603-1/10W-5%"))
    )
    (comp (ref "R3")
      (value "1k")
      (footprint "eagle-import:0603")
      (libsource (lib "eagle-import") (part "1KOHM-0603-1/10W-1%"))
    )
    (comp (ref "R4")
      (value "1k")
      (footprint "eagle-import:0603")
      (libsource (lib "eagle-import") (part "1KOHM-0603-1/10W-1%"))
    )
    (comp (ref "R5")
      (value "1k")
      (footprint "eagle-import:0603")
      (libsource (lib "eagle-import") (part "1KOHM-0603-1/10W-1%"))
    )
    (comp (ref "R6")
      (value "1k")
      (footprint "eagle-import:0603")
      (libsource (lib "eagle-import") (part "1KOHM-0603-1/10W-1%"))
    )
    (comp (ref "R7")
      (value "1k")
      (footprint "eagle-import:0603")
      (libsource (lib "eagle-import") (part "1KOHM-0603-1/10W-1%"))
    )
    (comp (ref "S1")
      (value "FSM2JSMA")
      (footprint "eagle-import:FSM2JSMA")
      (fields (field (name "COMMENT") "2-1437565-7") (field (name "MF") "TE Connectivity"))
      (libsource (lib "eagle-import") (part "FSM2JSMA"))
    )
    (comp (ref "Y1")
      (value "ABLS-16.000MHZ-B4-T")
      (footprint "eagle-import:ABLS-16.000MHZ-B4-T")
      (fields (field (name "MF") "Abracon") (field (name "MP") "ABLS-8.000MHZ-B2"))
      (libsource (lib "eagle-import") (part "ABLS-16.000MHZ-B4-T"))
    )
  )
  (nets
    (net (code "1") (name "+5V") (class "Default")
      (node (ref "C11") (pin "1") (pinfunction "1_1") (pintype "passive"))
      (node (ref "C12") (pin "1") (pinfunction "1_1") (pintype "passive"))
      (node (ref "C13") (pin "1") (pinfunction "1_1") (pintype "passive"))
      (node (ref "C14") (pin "1") (pinfunction "1_1") (pintype "passive"))
      (node (ref "C15") (pin "1") (pinfunction "1_1") (pintype "passive"))
      (node (ref "C2") (pin "1") (pinfunction "1_1") (pintype "passive"))
      (node (ref "C27") (pin "1") (pinfunction "1_1") (pintype "passive"))
      (node (ref "C3") (pin "1") (pinfunction "1_1") (pintype "passive"))
      (node (ref "C35") (pin "1") (pinfunction "1_1") (pintype "passive"))
      (node (ref "C6") (pin "1") (pinfunction "1_1") (pintype "passive"))
      (node (ref "C8") (pin "1") (pinfunction "1_1") (pintype "passive"))
      (node (ref "C9") (pin "1") (pinfunction "1_1") (pintype "passive"))
      (node (ref "IC1") (pin "10") (pinfunction "VCC_10") (pintype "power_in"))
      (node (ref "IC1") (pin "100") (pinfunction "AVCC_100") (pintype "power_in"))
      (node (ref "IC1") (pin "31") (pinfunction "VCC1_31") (pintype "power_in"))
      (node (ref "IC1") (pin "61") (pinfunction "VCC2_61") (pintype "power_in"))
      (node (ref "IC1") (pin "80") (pinfunction "VCC3_80") (pintype "power_in"))
      (node (ref "J17") (pin "3") (pinfunction "3_3") (pintype "passive"))
      (node (ref "J17") (pin "6") (pinfunction "6_6") (pintype "passive"))
      (node (ref "J18") (pin "3") (pinfunction "3_3") (pintype "passive"))
      (node (ref "J18") (pin "6") (pinfunction "6_6") (pintype "passive"))
      (node (ref "J19") (pin "4") (pinfunction "4_4") (pintype "passive"))
      (node (ref "J20") (pin "5") (pinfunction "5_5") (pintype "passive"))
      (node (ref "J20") (pin "8") (pinfunction "8_8") (pintype "passive"))
      (node (ref "J23") (pin "5") (pinfunction "5_5") (pintype "passive"))
      (node (ref "J23") (pin "6") (pinfunction "6_6") (pintype "passive"))
      (node (ref "JP1") (pin "4") (pinfunction "4_4") (pintype "passive"))
      (node (ref "JP1") (pin "5") (pinfunction "5_5") (pintype "passive"))
      (node (ref "JP11") (pin "2") (pinfunction "2_2") (pintype "passive"))
      (node (ref "JP2") (pin "4") (pinfunction "4_4") (pintype "passive"))
      (node (ref "JP2") (pin "5") (pinfunction "5_5") (pintype "passive"))
      (node (ref "R1") (pin "2") (pinfunction "2_2") (pintype "passive"))
      (node (ref "R11") (pin "2") (pinfunction "2_2") (pintype "passive"))
      (node (ref "R14") (pin "2") (pinfunction "2_2") (pintype "passive"))
      (node (ref "R15") (pin "2") (pinfunction "2_2") (pintype "passive"))
      (node (ref "R24") (pin "1") (pinfunction "1_1") (pintype "passive"))
      (node (ref "R25") (pin "1") (pinfunction "1_1") (pintype "passive"))
      (node (ref "R26") (pin "1") (pinfunction "1_1") (pintype "passive"))
      (node (ref "R27") (pin "1") (pinfunction "1_1") (pintype "passive"))
      (node (ref "R28") (pin "2") (pinfunction "2_2") (pintype "passive"))
      (node (ref "R29") (pin "2") (pinfunction "2_2") (pintype "passive"))
      (node (ref "R3") (pin "1") (pinfunction "1_1") (pintype "passive"))
      (node (ref "R8") (pin "2") (pinfunction "2_2") (pintype "passive"))
      (node (ref "TP18") (pin "P$1") (pinfunction "1_P$1") (pintype "bidirectional"))
      (node (ref "U1") (pin "1") (pinfunction "VDDA_1") (pintype "bidirectional"))
      (node (ref "U1") (pin "10") (pinfunction "VDDB_10") (pintype "bidirectional"))
      (node (ref "U10") (pin "3") (pinfunction "OUTPUT_3") (pintype "output"))
      (node (ref "U2") (pin "11") (pinfunction "STAT_DIS_11") (pintype "bidirectional"))
      (node (ref "U3") (pin "11") (pinfunction "STAT_DIS_11") (pintype "bidirectional"))
    )
    (net (code "2") (name "+12V") (class "Default")
      (node (ref "D7") (pin "1") (pinfunction "A_1") (pintype "passive"))
      (node (ref "D8") (pin "1") (pinfunction "A_1") (pintype "passive"))
      (node (ref "J14") (pin "1") (pinfunction "1_1") (pintype "passive"))
      (node (ref "J22") (pin "2") (pinfunction "2_2") (pintype "passive"))
      (node (ref "J23") (pin "7") (pinfunction "7_7") (pintype "passive"))
      (node (ref "J23") (pin "8") (pinfunction "8_8") (pintype "passive"))
      (node (ref "JP20") (pin "3") (pinfunction "3_3") (pintype "passive"))
      (node (ref "K1") (pin "A2") (pinfunction "A2_A2") (pintype "passive"))
      (node (ref "Q6") (pin "S") (pinfunction "S_S") (pintype "bidirectional"))
      (node (ref "R19") (pin "2") (pinfunction "2_2") (pintype "passive"))
      (node (ref "TP2") (pin "P$1") (pinfunction "1_P$1") (pintype "bidirectional"))
    )
    (net (code "3") (name "A1") (class "Default")
      (node (ref "J7") (pin "A1") (pinfunction "5_A1") (pintype "passive"))
      (node (ref "J8") (pin "3") (pinfunction "3_3") (pintype "passive"))
    )
    (net (code "4") (name "A2") (class "Default")
      (node (ref "J7") (pin "A2") (pinfunction "6_A2") (pintype "passive"))
      (node (ref "J8") (pin "2") (pinfunction "2_2") (pintype "passive"))
    )
    (net (code "5") (name "ADD_A12") (class "Default")
      (node (ref "IC1") (pin "85") (pinfunction "PK4(ADC12/PCINT20)_85") (pintype "bidirectional"))
      (node (ref "JP2") (pin "2") (pinfunction "2_2") (pintype "passive"))
    )
    (net (code "6") (name "ADD_A13") (class "Default")
      (node (ref "IC1") (pin "84") (pinfunction "PK5(ADC13/PCINT21)_84") (pintype "bidirectional"))
      (node (ref "JP2") (pin "3") (pinfunction "3_3") (pintype "passive"))
    )
    (net (code "7") (name "ADD_A14") (class "Default")
      (node (ref "IC1") (pin "83") (pinfunction "PK6(ADC14/PCINT22)_83") (pintype "bidirectional"))
      (node (ref "JP2") (pin "6") (pinfunction "6_6") (pintype "passive"))
    )
    (net (code "8") (name "ADD_A15") (class "Default")
      (node (ref "IC1") (pin "82") (pinfunction "PK7(ADC15/PCINT23)_82") (pintype "bidirectional"))
      (node (ref "JP2") (pin "7") (pinfunction "7_7") (pintype "passive"))
    )
    (net (code "9") (name "ADD_D22") (class "Default")
      (node (ref "IC1") (pin "78") (pinfunction "(AD0)PA0_78") (pintype "bidirectional"))
      (node (ref "JP1") (pin "2") (pinfunction "2_2") (pintype "passive"))
      (node (ref "R6") (pin "1") (pinfunction "1_1") (pintype "passive"))
    )
    (net (code "10") (name "ADD_D23") (class "Default")
      (node (ref "IC1") (pin "77") (pinfunction "(AD1)PA1_77") (pintype "bidirectional"))
      (node (ref "JP1") (pin "3") (pinfunction "3_3") (pintype "passive"))
      (node (ref "R4") (pin "1") (pinfunction "1_1") (pintype "passive"))
    )
    (net (code "11") (name "ADD_D24") (class "Default")
      (node (ref "IC1") (pin "76") (pinfunction "(AD2)PA2_76") (pintype "bidirectional"))
      (node (ref "JP1") (pin "6") (pinfunction "6_6") (pintype "passive"))
      (node (ref "R7") (pin "1") (pinfunction "1_1") (pintype "passive"))
    )
    (net (code "12") (name "ADD_D25") (class "Default")
      (node (ref "IC1") (pin "75") (pinfunction "(AD3)PA3_75") (pintype "bidirectional"))
      (node (ref "JP1") (pin "7") (pinfunction "7_7") (pintype "passive"))
      (node (ref "R5") (pin "1") (pinfunction "1_1") (pintype "passive"))
    )
    (net (code "13") (name "AREF") (class "Default")
      (node (ref "C10") (pin "1") (pinfunction "1_1") (pintype "passive"))
      (node (ref "C7") (pin "1") (pinfunction "1_1") (pintype "passive"))
      (node (ref "IC1") (pin "98") (pinfunction "AREF_98") (pintype "bidirectional"))
    )
    (net (code "14") (name "B1") (class "Default")
      (node (ref "J7") (pin "B1") (pinfunction "4_B1") (pintype "passive"))
      (node (ref "J8") (pin "4") (pinfunction "4_4") (pintype "passive"))
    )
    (net (code "15") (name "B2") (class "Default")
      (node (ref "J7") (pin "B2") (pinfunction "3_B2") (pintype "passive"))
      (node (ref "J8") (pin "5") (pinfunction "5_5") (pintype "passive"))
    )
    (net (code "16") (name "BLENDER0-") (class "Default")
      (node (ref "D1") (pin "1") (pinfunction "A_1") (pintype "passive"))
      (node (ref "J12") (pin "P$2") (pinfunction "2_P$2") (pintype "passive"))
      (node (ref "Q4") (pin "2") (pinfunction "D_2") (pintype "bidirectional"))
    )
    (net (code "17") (name "BLENDER0_EN") (class "Default")
      (node (ref "IC1") (pin "51") (pinfunction "(WR)PG0_51") (pintype "bidirectional"))
      (node (ref "J9") (pin "1") (pinfunction "1_1") (pintype "passive"))
      (node (ref "U4") (pin "1") (pinfunction "1_1") (pintype "passive"))
    )
    (net (code "18") (name "BLENDER0_GATE") (class "Default")
      (node (ref "J10") (pin "1") (pinfunction "1_1") (pintype "passive"))
      (node (ref "Q4") (pin "1") (pinfunction "G_1") (pintype "bidirectional"))
      (node (ref "R20") (pin "2") (pinfunction "2_2") (pintype "passive"))
      (node (ref "U4") (pin "3") (pinfunction "3_3") (pintype "passive"))
    )
    (net (code "19") (name "BLENDER1-") (class "Default")
      (node (ref "D2") (pin "1") (pinfunction "A_1") (pintype "passive"))
      (node (ref "J13") (pin "P$2") (pinfunction "2_P$2") (pintype "passive"))
      (node (ref "Q5") (pin "2") (pinfunction "D_2") (pintype "bidirectional"))
    )
    (net (code "20") (name "BLENDER1_EN") (class "Default")
      (node (ref "IC1") (pin "52") (pinfunction "(RD)PG1_52") (pintype "bidirectional"))
      (node (ref "J9") (pin "2") (pinfunction "2_2") (pintype "passive"))
      (node (ref "U5") (pin "1") (pinfunction "1_1") (pintype "passive"))
    )
    (net (code "21") (name "BLENDER1_GATE") (class "Default")
      (node (ref "J10") (pin "2") (pinfunction "2_2") (pintype "passive"))
      (node (ref "Q5") (pin "1") (pinfunction "G_1") (pintype "bidirectional"))
      (node (ref "R21") (pin "2") (pinfunction "2_2") (pintype "passive"))
      (node (ref "U5") (pin "3") (pinfunction "3_3") (pintype "passive"))
    )
    (net (code "22") (name "CAROUSEL_POS") (class "Default")
      (node (ref "IC1") (pin "95") (pinfunction "(ADC2)PF2_95") (pintype "bidirectional"))
      (node (ref "J18") (pin "4") (pinfunction "4_4") (pintype "passive"))
      (node (ref "R24") (pin "2") (pinfunction "2_2") (pintype "passive"))
    )
    (net (code "23") (name "COOLANT-") (class "Default")
      (node (ref "J14") (pin "2") (pinfunction "2_2") (pintype "passive"))
      (node (ref "Q3") (pin "2") (pinfunction "D_2") (pintype "bidirectional"))
    )
    (net (code "24") (name "COOLANT_EN") (class "Default")
      (node (ref "IC1") (pin "54") (pinfunction "(A9)PC1_54") (pintype "bidirectional"))
      (node (ref "Q2") (pin "S") (pinfunction "S_S") (pintype "passive"))
      (node (ref "R18") (pin "1") (pinfunction "1_1") (pintype "passive"))
    )
    (net (code "25") (name "COOLANT_GATE") (class "Default")
      (node (ref "Q2") (pin "D") (pinfunction "D_D") (pintype "passive"))
      (node (ref "Q3") (pin "1") (pinfunction "G_1") (pintype "bidirectional"))
      (node (ref "R19") (pin "1") (pinfunction "1_1") (pintype "passive"))
    )
    (net (code "26") (name "CUP_MASS0") (class "Default")
      (node (ref "IC1") (pin "93") (pinfunction "(ADC4/TCK)PF4_93") (pintype "bidirectional"))
      (node (ref "J17") (pin "2") (pinfunction "2_2") (pintype "passive"))
    )
    (net (code "27") (name "CUP_MASS1") (class "Default")
      (node (ref "IC1") (pin "92") (pinfunction "(ADC5/TMS)PF5_92") (pintype "bidirectional"))
      (node (ref "J17") (pin "5") (pinfunction "5_5") (pintype "passive"))
    )
    (net (code "28") (name "CURRSENS0-") (class "Default")
      (node (ref "Q4") (pin "3") (pinfunction "S_3") (pintype "bidirectional"))
      (node (ref "R23") (pin "2") (pinfunction "2_2") (pintype "passive"))
      (node (ref "U8") (pin "4") (pinfunction "IN+_4") (pintype "input"))
    )
    (net (code "29") (name "CURRSENS1-") (class "Default")
      (node (ref "Q5") (pin "3") (pinfunction "S_3") (pintype "bidirectional"))
      (node (ref "R22") (pin "2") (pinfunction "2_2") (pintype "passive"))
      (node (ref "U6") (pin "4") (pinfunction "IN+_4") (pintype "input"))
    )
    (net (code "30") (name "CURR_SENS0") (class "Default")
      (node (ref "C20") (pin "1") (pinfunction "1_1") (pintype "passive"))
      (node (ref "IC1") (pin "91") (pinfunction "(ADC6/TDO)PF6_91") (pintype "bidirectional"))
      (node (ref "J2") (pin "1") (pinfunction "1_1") (pintype "passive"))
      (node (ref "TP1") (pin "P$1") (pinfunction "1_P$1") (pintype "bidirectional"))
      (node (ref "U6") (pin "6") (pinfunction "OUT_6") (pintype "output"))
    )
    (net (code "31") (name "CURR_SENS1") (class "Default")
      (node (ref "C24") (pin "1") (pinfunction "1_1") (pintype "passive"))
      (node (ref "IC1") (pin "90") (pinfunction "(ADC7/TDI)PF7_90") (pintype "bidirectional"))
      (node (ref "J2") (pin "2") (pinfunction "2_2") (pintype "passive"))
      (node (ref "TP20") (pin "P$1") (pinfunction "1_P$1") (pintype "bidirectional"))
      (node (ref "U8") (pin "6") (pinfunction "OUT_6") (pintype "output"))
    )
    (net (code "32") (name "DIR") (class "Default")
      (node (ref "IC1") (pin "25") (pinfunction "(OC1B/PCINT6)PB6_25") (pintype "bidirectional"))
      (node (ref "J7") (pin "DIR") (pinfunction "9_DIR") (pintype "passive"))
    )
    (net (code "33") (name "DSCL+") (class "Default")
      (node (ref "J3") (pin "5") (pinfunction "5_5") (pintype "bidirectional"))
      (node (ref "J4") (pin "5") (pinfunction "5_5") (pintype "bidirectional"))
      (node (ref "JP16") (pin "1") (pinfunction "1_1") (pintype "passive"))
      (node (ref "JP16") (pin "2") (pinfunction "2_2") (pintype "passive"))
      (node (ref "JP18") (pin "1") (pinfunction "1_1") (pintype "passive"))
      (node (ref "JP18") (pin "2") (pinfunction "2_2") (pintype "passive"))
      (node (ref "JP3") (pin "1") (pinfunction "1_1") (pintype "passive"))
      (node (ref "JP5") (pin "1") (pinfunction "1_1") (pintype "passive"))
      (node (ref "JP7") (pin "2") (pinfunction "2_2") (pintype "passive"))
      (node (ref "JP9") (pin "2") (pinfunction "2_2") (pintype "passive"))
      (node (ref "R8") (pin "1") (pinfunction "1_1") (pintype "passive"))
      (node (ref "R9") (pin "2") (pinfunction "2_2") (pintype "passive"))
      (node (ref "TP10") (pin "P$1") (pinfunction "1_P$1") (pintype "bidirectional"))
      (node (ref "U1") (pin "7") (pinfunction "DSCL+_7") (pintype "bidirectional"))
    )
    (net (code "34") (name "DSCL-") (class "Default")
      (node (ref "J3") (pin "4") (pinfunction "4_4") (pintype "bidirectional"))
      (node (ref "J4") (pin "4") (pinfunction "4_4") (pintype "bidirectional"))
      (node (ref "JP12") (pin "1") (pinfunction "1_1") (pintype "passive"))
      (node (ref "JP12") (pin "2") (pinfunction "2_2") (pintype "passive"))
      (node (ref "JP14") (pin "1") (pinfunction "1_1") (pintype "passive"))
      (node (ref "JP14") (pin "2") (pinfunction "2_2") (pintype "passive"))
      (node (ref "JP3") (pin "2") (pinfunction "2_2") (pintype "passive"))
      (node (ref "JP5") (pin "2") (pinfunction "2_2") (pintype "passive"))
      (node (ref "JP7") (pin "1") (pinfunction "1_1") (pintype "passive"))
      (node (ref "JP9") (pin "1") (pinfunction "1_1") (pintype "passive"))
      (node (ref "R10") (pin "2") (pinfunction "2_2") (pintype "passive"))
      (node (ref "R9") (pin "1") (pinfunction "1_1") (pintype "passive"))
      (node (ref "TP11") (pin "P$1") (pinfunction "1_P$1") (pintype "bidirectional"))
      (node (ref "U1") (pin "6") (pinfunction "DSCL-_6") (pintype "bidirectional"))
    )
    (net (code "35") (name "DSDA+") (class "Default")
      (node (ref "J3") (pin "2") (pinfunction "2_2") (pintype "bidirectional"))
      (node (ref "J4") (pin "2") (pinfunction "2_2") (pintype "bidirectional"))
      (node (ref "JP10") (pin "2") (pinfunction "2_2") (pintype "passive"))
      (node (ref "JP17") (pin "1") (pinfunction "1_1") (pintype "passive"))
      (node (ref "JP17") (pin "2") (pinfunction "2_2") (pintype "passive"))
      (node (ref "JP19") (pin "1") (pinfunction "1_1") (pintype "passive"))
      (node (ref "JP19") (pin "2") (pinfunction "2_2") (pintype "passive"))
      (node (ref "JP4") (pin "1") (pinfunction "1_1") (pintype "passive"))
      (node (ref "JP6") (pin "1") (pinfunction "1_1") (pintype "passive"))
      (node (ref "JP8") (pin "2") (pinfunction "2_2") (pintype "passive"))
      (node (ref "R11") (pin "1") (pinfunction "1_1") (pintype "passive"))
      (node (ref "R12") (pin "2") (pinfunction "2_2") (pintype "passive"))
      (node (ref "TP12") (pin "P$1") (pinfunction "1_P$1") (pintype "bidirectional"))
      (node (ref "U1") (pin "8") (pinfunction "DSDA+_8") (pintype "bidirectional"))
    )
    (net (code "36") (name "DSDA-") (class "Default")
      (node (ref "J3") (pin "1") (pinfunction "1_1") (pintype "bidirectional"))
      (node (ref "J4") (pin "1") (pinfunction "1_1") (pintype "bidirectional"))
      (node (ref "JP10") (pin "1") (pinfunction "1_1") (pintype "passive"))
      (node (ref "JP13") (pin "1") (pinfunction "1_1") (pintype "passive"))
      (node (ref "JP13") (pin "2") (pinfunction "2_2") (pintype "passive"))
      (node (ref "JP15") (pin "1") (pinfunction "1_1") (pintype "passive"))
      (node (ref "JP15") (pin "2") (pinfunction "2_2") (pintype "passive"))
      (node (ref "JP4") (pin "2") (pinfunction "2_2") (pintype "passive"))
      (node (ref "JP6") (pin "2") (pinfunction "2_2") (pintype "passive"))
      (node (ref "JP8") (pin "1") (pinfunction "1_1") (pintype "passive"))
      (node (ref "R12") (pin "1") (pinfunction "1_1") (pintype "passive"))
      (node (ref "R13") (pin "2") (pinfunction "2_2") (pintype "passive"))
      (node (ref "TP13") (pin "P$1") (pinfunction "1_P$1") (pintype "bidirectional"))
      (node (ref "U1") (pin "9") (pinfunction "DSDA-_9") (pintype "bidirectional"))
    )
    (net (code "37") (name "ELEV_CS") (class "Default")
      (node (ref "U9") (pin "13") (pinfunction "CS_13") (pintype "bidirectional"))
    )
    (net (code "38") (name "ELEV_ENC_A") (class "Default")
      (node (ref "IC1") (pin "45") (pinfunction "(RXD1/INT2)PD2_45") (pintype "bidirectional"))
      (node (ref "J20") (pin "6") (pinfunction "6_6") (pintype "passive"))
      (node (ref "R26") (pin "2") (pinfunction "2_2") (pintype "passive"))
    )
    (net (code "39") (name "ELEV_ENC_B") (class "Default")
      (node (ref "IC1") (pin "46") (pinfunction "(TXD1/INT3)PD3_46") (pintype "bidirectional"))
      (node (ref "J20") (pin "3") (pinfunction "3_3") (pintype "passive"))
      (node (ref "R27") (pin "2") (pinfunction "2_2") (pintype "passive"))
    )
    (net (code "40") (name "ELEV_INA") (class "Default")
      (node (ref "IC1") (pin "16") (pinfunction "PH4(OC4B)_16") (pintype "bidirectional"))
      (node (ref "U9") (pin "3") (pinfunction "IN_A_3") (pintype "input"))
    )
    (net (code "41") (name "ELEV_INB") (class "Default")
      (node (ref "IC1") (pin "17") (pinfunction "PH5(OC4C)_17") (pintype "bidirectional"))
      (node (ref "U9") (pin "6") (pinfunction "IN_B_6") (pintype "input"))
    )
    (net (code "42") (name "ELEV_OUT_A") (class "Default")
      (node (ref "J16") (pin "1") (pinfunction "1_1") (pintype "passive"))
      (node (ref "U9") (pin "15") (pinfunction "OUT_A-1_15") (pintype "output"))
      (node (ref "U9") (pin "2") (pinfunction "OUT_A_2") (pintype "output"))
    )
    (net (code "43") (name "ELEV_OUT_B") (class "Default")
      (node (ref "J16") (pin "2") (pinfunction "2_2") (pintype "passive"))
      (node (ref "U9") (pin "10") (pinfunction "OUT_B-1_10") (pintype "output"))
      (node (ref "U9") (pin "7") (pinfunction "OUT_B_7") (pintype "output"))
    )
    (net (code "44") (name "ELEV_PWM") (class "Default")
      (node (ref "IC1") (pin "15") (pinfunction "PH3(OC4A)_15") (pintype "bidirectional"))
      (node (ref "U9") (pin "11") (pinfunction "PWM_11") (pintype "bidirectional"))
    )
    (net (code "45") (name "EN") (class "Default")
      (node (ref "U1") (pin "2") (pinfunction "EN_2") (pintype "bidirectional"))
    )
    (net (code "46") (name "FROZEN1") (class "Default")
      (node (ref "J5") (pin "8") (pinfunction "8_8") (pintype "passive"))
      (node (ref "U2") (pin "22") (pinfunction "OUT1-2_22") (pintype "output"))
      (node (ref "U2") (pin "23") (pinfunction "OUT1_23") (pintype "output"))
      (node (ref "U2") (pin "24") (pinfunction "OUT1-1_24") (pintype "output"))
    )
    (net (code "47") (name "FROZEN1_EN") (class "Default")
      (node (ref "IC1") (pin "5") (pinfunction "(OC3A/AIN1)PE3_5") (pintype "bidirectional"))
      (node (ref "U2") (pin "3") (pinfunction "IN1_3") (pintype "bidirectional"))
    )
    (net (code "48") (name "FROZEN2") (class "Default")
      (node (ref "J5") (pin "6") (pinfunction "6_6") (pintype "passive"))
      (node (ref "U2") (pin "19") (pinfunction "OUT2-1_19") (pintype "output"))
      (node (ref "U2") (pin "20") (pinfunction "OUT2_20") (pintype "output"))
      (node (ref "U2") (pin "21") (pinfunction "OUT2-2_21") (pintype "output"))
    )
    (net (code "49") (name "FROZEN2_EN") (class "Default")
      (node (ref "IC1") (pin "40") (pinfunction "PL5(OC5C)_40") (pintype "bidirectional"))
      (node (ref "U2") (pin "5") (pinfunction "IN2_5") (pintype "input"))
    )
    (net (code "50") (name "FROZEN3") (class "Default")
      (node (ref "J5") (pin "4") (pinfunction "4_4") (pintype "passive"))
      (node (ref "U2") (pin "16") (pinfunction "OUT3-2_16") (pintype "output"))
      (node (ref "U2") (pin "17") (pinfunction "OUT3-1_17") (pintype "output"))
      (node (ref "U2") (pin "18") (pinfunction "OUT3_18") (pintype "output"))
    )
    (net (code "51") (name "FROZEN3_EN") (class "Default")
      (node (ref "IC1") (pin "39") (pinfunction "PL4(OC5B)_39") (pintype "bidirectional"))
      (node (ref "U2") (pin "7") (pinfunction "IN3_7") (pintype "input"))
    )
    (net (code "52") (name "FROZEN4") (class "Default")
      (node (ref "J5") (pin "2") (pinfunction "2_2") (pintype "passive"))
      (node (ref "U2") (pin "13") (pinfunction "OUT4-1_13") (pintype "output"))
      (node (ref "U2") (pin "14") (pinfunction "OUT4_14") (pintype "output"))
      (node (ref "U2") (pin "15") (pinfunction "OUT4-2_15") (pintype "output"))
    )
    (net (code "53") (name "FROZEN4_EN") (class "Default")
      (node (ref "IC1") (pin "38") (pinfunction "PL3(OC5A)_38") (pintype "bidirectional"))
      (node (ref "U2") (pin "9") (pinfunction "IN4_9") (pintype "input"))
    )
    (net (code "54") (name "FUSE0-") (class "Default")
      (node (ref "D1") (pin "2") (pinfunction "C_2") (pintype "passive"))
      (node (ref "F1") (pin "2") (pinfunction "2_2") (pintype "passive"))
      (node (ref "J12") (pin "P$1") (pinfunction "1_P$1") (pintype "passive"))
    )
    (net (code "55") (name "FUSE1-") (class "Default")
      (node (ref "D2") (pin "2") (pinfunction "C_2") (pintype "passive"))
      (node (ref "F2") (pin "2") (pinfunction "2_2") (pintype "passive"))
      (node (ref "J13") (pin "P$1") (pinfunction "1_P$1") (pintype "passive"))
    )
    (net (code "56") (name "F_STAT1") (class "Default")
      (node (ref "U2") (pin "4") (pinfunction "STAT1_4") (pintype "bidirectional"))
    )
    (net (code "57") (name "F_STAT2") (class "Default")
      (node (ref "U2") (pin "6") (pinfunction "STAT2_6") (pintype "bidirectional"))
    )
    (net (code "58") (name "F_STAT3") (class "Default")
      (node (ref "U2") (pin "8") (pinfunction "STAT3_8") (pintype "bidirectional"))
    )
    (net (code "59") (name "F_STAT4") (class "Default")
      (node (ref "U2") (pin "10") (pinfunction "STAT4_10") (pintype "bidirectional"))
    )
    (net (code "60") (name "GND") (class "Default")
      (node (ref "C1") (pin "2") (pinfunction "2_2") (pintype "passive"))
      (node (ref "C10") (pin "2") (pinfunction "2_2") (pintype "passive"))
      (node (ref "C11") (pin "2") (pinfunction "2_2") (pintype "passive"))
      (node (ref "C12") (pin "2") (pinfunction "2_2") (pintype "passive"))
      (node (ref "C13") (pin "2") (pinfunction "2_2") (pintype "passive"))
      (node (ref "C14") (pin "2") (pinfunction "2_2") (pintype "passive"))
      (node (ref "C15") (pin "2") (pinfunction "2_2") (pintype "passive"))
      (node (ref "C16") (pin "-") (pinfunction "-_-") (pintype "passive"))
      (node (ref "C17") (pin "-") (pinfunction "-_-") (pintype "passive"))
      (node (ref "C18") (pin "-") (pinfunction "-_-") (pintype "passive"))
      (node (ref "C19") (pin "2") (pinfunction "2_2") (pintype "passive"))
      (node (ref "C2") (pin "2") (pinfunction "2_2") (pintype "passive"))
      (node (ref "C20") (pin "2") (pinfunction "2_2") (pintype "passive"))
      (node (ref "C21") (pin "2") (pinfunction "2_2") (pintype "passive"))
      (node (ref "C22") (pin "-") (pinfunction "-_-") (pintype "passive"))
      (node (ref "C23") (pin "2") (pinfunction "2_2") (pintype "passive"))
      (node (ref "C24") (pin "2") (pinfunction "2_2") (pintype "passive"))
      (node (ref "C25") (pin "2") (pinfunction "2_2") (pintype "passive"))
      (node (ref "C26") (pin "-") (pinfunction "-_-") (pintype "passive"))
      (node (ref "C27") (pin "2") (pinfunction "2_2") (pintype "passive"))
      (node (ref "C28") (pin "2") (pinfunction "2_2") (pintype "passive"))
      (node (ref "C29") (pin "2") (pinfunction "2_2") (pintype "passive"))
      (node (ref "C3") (pin "2") (pinfunction "2_2") (pintype "passive"))
      (node (ref "C33") (pin "2") (pinfunction "2_2") (pintype "passive"))
      (node (ref "C34") (pin "2") (pinfunction "2_2") (pintype "passive"))
      (node (ref "C35") (pin "2") (pinfunction "2_2") (pintype "passive"))
      (node (ref "C36") (pin "2") (pinfunction "2_2") (pintype "passive"))
      (node (ref "C37") (pin "2") (pinfunction "2_2") (pintype "passive"))
      (node (ref "C38") (pin "2") (pinfunction "2_2") (pintype "passive"))
      (node (ref "C4") (pin "1") (pinfunction "1_1") (pintype "passive"))
      (node (ref "C5") (pin "1") (pinfunction "1_1") (pintype "passive"))
      (node (ref "C6") (pin "2") (pinfunction "2_2") (pintype "passive"))
      (node (ref "C7") (pin "2") (pinfunction "2_2") (pintype "passive"))
      (node (ref "C8") (pin "2") (pinfunction "2_2") (pintype "passive"))
      (node (ref "C9") (pin "2") (pinfunction "2_2") (pintype "passive"))
      (node (ref "IC1") (pin "11") (pinfunction "GND_11") (pintype "power_in"))
      (node (ref "IC1") (pin "32") (pinfunction "GND1_32") (pintype "power_in"))
      (node (ref "IC1") (pin "62") (pinfunction "GND2_62") (pintype "power_in"))
      (node (ref "IC1") (pin "81") (pinfunction "GND3_81") (pintype "power_in"))
      (node (ref "IC1") (pin "99") (pinfunction "AGND_99") (pintype "power_in"))
      (node (ref "J17") (pin "1") (pinfunction "1_1") (pintype "passive"))
      (node (ref "J17") (pin "4") (pinfunction "4_4") (pintype "passive"))
      (node (ref "J18") (pin "2") (pinfunction "2_2") (pintype "passive"))
      (node (ref "J18") (pin "5") (pinfunction "5_5") (pintype "passive"))
      (node (ref "J19") (pin "1") (pinfunction "1_1") (pintype "passive"))
      (node (ref "J19") (pin "6") (pinfunction "6_6") (pintype "passive"))
      (node (ref "J20") (pin "1") (pinfunction "1_1") (pintype "passive"))
      (node (ref "J20") (pin "4") (pinfunction "4_4") (pintype "passive"))
      (node (ref "J20") (pin "7") (pinfunction "7_7") (pintype "passive"))
      (node (ref "J22") (pin "1") (pinfunction "1_1") (pintype "passive"))
      (node (ref "J23") (pin "1") (pinfunction "1_1") (pintype "passive"))
      (node (ref "J23") (pin "2") (pinfunction "2_2") (pintype "passive"))
      (node (ref "J23") (pin "3") (pinfunction "3_3") (pintype "passive"))
      (node (ref "J23") (pin "4") (pinfunction "4_4") (pintype "passive"))
      (node (ref "J3") (pin "3") (pinfunction "3_3") (pintype "bidirectional"))
      (node (ref "J3") (pin "6") (pinfunction "6_6") (pintype "bidirectional"))
      (node (ref "J3") (pin "7") (pinfunction "7_7") (pintype "bidirectional"))
      (node (ref "J3") (pin "8") (pinfunction "8_8") (pintype "bidirectional"))
      (node (ref "J4") (pin "3") (pinfunction "3_3") (pintype "bidirectional"))
      (node (ref "J4") (pin "6") (pinfunction "6_6") (pintype "bidirectional"))
      (node (ref "J4") (pin "7") (pinfunction "7_7") (pintype "bidirectional"))
      (node (ref "J4") (pin "8") (pinfunction "8_8") (pintype "bidirectional"))
      (node (ref "J5") (pin "1") (pinfunction "1_1") (pintype "passive"))
      (node (ref "J5") (pin "3") (pinfunction "3_3") (pintype "passive"))
      (node (ref "J5") (pin "5") (pinfunction "5_5") (pintype "passive"))
      (node (ref "J5") (pin "7") (pinfunction "7_7") (pintype "passive"))
      (node (ref "J6") (pin "1") (pinfunction "1_1") (pintype "passive"))
      (node (ref "J6") (pin "3") (pinfunction "3_3") (pintype "passive"))
      (node (ref "J6") (pin "5") (pinfunction "5_5") (pintype "passive"))
      (node (ref "J6") (pin "7") (pinfunction "7_7") (pintype "passive"))
      (node (ref "J7") (pin "GND") (pinfunction "2_GND") (pintype "passive"))
      (node (ref "J7") (pin "GND1") (pinfunction "8_GND1") (pintype "passive"))
      (node (ref "JP1") (pin "1") (pinfunction "1_1") (pintype "passive"))
      (node (ref "JP1") (pin "8") (pinfunction "8_8") (pintype "passive"))
      (node (ref "JP11") (pin "6") (pinfunction "6_6") (pintype "passive"))
      (node (ref "JP2") (pin "1") (pinfunction "1_1") (pintype "passive"))
      (node (ref "JP2") (pin "8") (pinfunction "8_8") (pintype "passive"))
      (node (ref "L1") (pin "P$2") (pinfunction "2_P$2") (pintype "passive"))
      (node (ref "LED1") (pin "C") (pinfunction "C_C") (pintype "passive"))
      (node (ref "LED2") (pin "C") (pinfunction "C_C") (pintype "passive"))
      (node (ref "LED3") (pin "C") (pinfunction "C_C") (pintype "passive"))
      (node (ref "LED4") (pin "C") (pinfunction "C_C") (pintype "passive"))
      (node (ref "LED5") (pin "C") (pinfunction "C_C") (pintype "passive"))
      (node (ref "Q1") (pin "S") (pinfunction "S_S") (pintype "passive"))
      (node (ref "Q3") (pin "3") (pinfunction "S_3") (pintype "bidirectional"))
      (node (ref "Q6") (pin "G") (pinfunction "G_G") (pintype "bidirectional"))
      (node (ref "R10") (pin "1") (pinfunction "1_1") (pintype "passive"))
      (node (ref "R13") (pin "1") (pinfunction "1_1") (pintype "passive"))
      (node (ref "R16") (pin "1") (pinfunction "1_1") (pintype "passive"))
      (node (ref "R17") (pin "1") (pinfunction "1_1") (pintype "passive"))
      (node (ref "R20") (pin "1") (pinfunction "1_1") (pintype "passive"))
      (node (ref "R21") (pin "1") (pinfunction "1_1") (pintype "passive"))
      (node (ref "S1") (pin "3") (pinfunction "3_3") (pintype "passive"))
      (node (ref "S1") (pin "4") (pinfunction "4_4") (pintype "passive"))
      (node (ref "TP3") (pin "P$1") (pinfunction "1_P$1") (pintype "bidirectional"))
      (node (ref "TP4") (pin "P$1") (pinfunction "1_P$1") (pintype "bidirectional"))
      (node (ref "TP5") (pin "P$1") (pinfunction "1_P$1") (pintype "bidirectional"))
      (node (ref "TP6") (pin "P$1") (pinfunction "1_P$1") (pintype "bidirectional"))
      (node (ref "U1") (pin "5") (pinfunction "GND_5") (pintype "bidirectional"))
      (node (ref "U10") (pin "2") (pinfunction "GND_2") (pintype "power_in"))
      (node (ref "U10") (pin "4") (pinfunction "GND_4") (pintype "power_in"))
      (node (ref "U11") (pin "2") (pinfunction "GND_2") (pintype "power_in"))
      (node (ref "U11") (pin "4") (pinfunction "GND_4") (pintype "power_in"))
      (node (ref "U2") (pin "2") (pinfunction "GND_2") (pintype "power_in"))
      (node (ref "U3") (pin "2") (pinfunction "GND_2") (pintype "power_in"))
      (node (ref "U6") (pin "1") (pinfunction "REF_1") (pintype "input"))
      (node (ref "U6") (pin "2") (pinfunction "GND_2") (pintype "passive"))
      (node (ref "U7") (pin "1") (pinfunction "GND_A_1") (pintype "power_in"))
      (node (ref "U7") (pin "14") (pinfunction "SEL0_14") (pintype "bidirectional"))
      (node (ref "U7") (pin "16") (pinfunction "GND_A-1_16") (pintype "power_in"))
      (node (ref "U7") (pin "8") (pinfunction "GND_B_8") (pintype "power_in"))
      (node (ref "U7") (pin "9") (pinfunction "GND_B-1_9") (pintype "power_in"))
      (node (ref "U8") (pin "1") (pinfunction "REF_1") (pintype "input"))
      (node (ref "U8") (pin "2") (pinfunction "GND_2") (pintype "passive"))
      (node (ref "U9") (pin "1") (pinfunction "GND_A_1") (pintype "power_in"))
      (node (ref "U9") (pin "14") (pinfunction "SEL0_14") (pintype "bidirectional"))
      (node (ref "U9") (pin "16") (pinfunction "GND_A-1_16") (pintype "power_in"))
      (node (ref "U9") (pin "8") (pinfunction "GND_B_8") (pintype "power_in"))
      (node (ref "U9") (pin "9") (pinfunction "GND_B-1_9") (pintype "power_in"))
    )
    (net (code "61") (name "GND2") (class "Default")
      (node (ref "C30") (pin "-") (pinfunction "-_-") (pintype "passive"))
      (node (ref "C31") (pin "-") (pinfunction "-_-") (pintype "passive"))
      (node (ref "C32") (pin "-") (pinfunction "-_-") (pintype "passive"))
      (node (ref "D4") (pin "1") (pinfunction "A_1") (pintype "passive"))
      (node (ref "D4") (pin "3") (pinfunction "A_3") (pintype "passive"))
      (node (ref "D6") (pin "1") (pinfunction "A_1") (pintype "passive"))
      (node (ref "D6") (pin "3") (pinfunction "A_3") (pintype "passive"))
      (node (ref "L1") (pin "P$1") (pinfunction "1_P$1") (pintype "passive"))
      (node (ref "R22") (pin "1") (pinfunction "1_1") (pintype "passive"))
      (node (ref "R23") (pin "1") (pinfunction "1_1") (pintype "passive"))
      (node (ref "U6") (pin "5") (pinfunction "IN-_5") (pintype "input"))
      (node (ref "U8") (pin "5") (pinfunction "IN-_5") (pintype "input"))
    )
    (net (code "62") (name "HEATPUMP_EN") (class "Default")
      (node (ref "IC1") (pin "55") (pinfunction "(A10)PC2_55") (pintype "bidirectional"))
      (node (ref "Q1") (pin "G") (pinfunction "G_G") (pintype "passive"))
    )
    (net (code "63") (name "LIMIT_SENSE") (class "Default")
      (node (ref "IC1") (pin "70") (pinfunction "(ALE)PG2_70") (pintype "bidirectional"))
      (node (ref "J18") (pin "1") (pinfunction "1_1") (pintype "passive"))
      (node (ref "R25") (pin "2") (pinfunction "2_2") (pintype "passive"))
    )
    (net (code "64") (name "LIQUID1") (class "Default")
      (node (ref "J6") (pin "8") (pinfunction "8_8") (pintype "passive"))
      (node (ref "U3") (pin "22") (pinfunction "OUT1-2_22") (pintype "output"))
      (node (ref "U3") (pin "23") (pinfunction "OUT1_23") (pintype "output"))
      (node (ref "U3") (pin "24") (pinfunction "OUT1-1_24") (pintype "output"))
    )
    (net (code "65") (name "LIQUID1_EN") (class "Default")
      (node (ref "IC1") (pin "37") (pinfunction "PL2(T5)_37") (pintype "bidirectional"))
      (node (ref "U3") (pin "3") (pinfunction "IN1_3") (pintype "bidirectional"))
    )
    (net (code "66") (name "LIQUID2") (class "Default")
      (node (ref "J6") (pin "6") (pinfunction "6_6") (pintype "passive"))
      (node (ref "U3") (pin "19") (pinfunction "OUT2-1_19") (pintype "output"))
      (node (ref "U3") (pin "20") (pinfunction "OUT2_20") (pintype "output"))
      (node (ref "U3") (pin "21") (pinfunction "OUT2-2_21") (pintype "output"))
    )
    (net (code "67") (name "LIQUID2_EN") (class "Default")
      (node (ref "IC1") (pin "36") (pinfunction "PL1(ICP5)_36") (pintype "bidirectional"))
      (node (ref "U3") (pin "5") (pinfunction "IN2_5") (pintype "input"))
    )
    (net (code "68") (name "LIQUID3") (class "Default")
      (node (ref "J6") (pin "4") (pinfunction "4_4") (pintype "passive"))
      (node (ref "U3") (pin "16") (pinfunction "OUT3-2_16") (pintype "output"))
      (node (ref "U3") (pin "17") (pinfunction "OUT3-1_17") (pintype "output"))
      (node (ref "U3") (pin "18") (pinfunction "OUT3_18") (pintype "output"))
    )
    (net (code "69") (name "LIQUID3_EN") (class "Default")
      (node (ref "IC1") (pin "35") (pinfunction "PL0(ICP4)_35") (pintype "bidirectional"))
      (node (ref "U3") (pin "7") (pinfunction "IN3_7") (pintype "input"))
    )
    (net (code "70") (name "L_STAT1") (class "Default")
      (node (ref "U3") (pin "4") (pinfunction "STAT1_4") (pintype "bidirectional"))
    )
    (net (code "71") (name "L_STAT2") (class "Default")
      (node (ref "U3") (pin "6") (pinfunction "STAT2_6") (pintype "bidirectional"))
    )
    (net (code "72") (name "L_STAT3") (class "Default")
      (node (ref "U3") (pin "8") (pinfunction "STAT3_8") (pintype "bidirectional"))
    )
    (net (code "73") (name "M+") (class "Default")
      (node (ref "D3") (pin "1") (pinfunction "A_1") (pintype "passive"))
      (node (ref "D3") (pin "3") (pinfunction "A_3") (pintype "passive"))
      (node (ref "D4") (pin "4") (pinfunction "C_4") (pintype "passive"))
      (node (ref "F3") (pin "2") (pinfunction "2_2") (pintype "passive"))
      (node (ref "K1") (pin "NO") (pinfunction "NO_NO") (pintype "passive"))
    )
    (net (code "74") (name "M+_IN") (class "Default")
      (node (ref "F3") (pin "1") (pinfunction "1_1") (pintype "passive"))
      (node (ref "J21") (pin "2") (pinfunction "2_2") (pintype "passive"))
    )
    (net (code "75") (name "M-") (class "Default")
      (node (ref "D5") (pin "1") (pinfunction "A_1") (pintype "passive"))
      (node (ref "D5") (pin "3") (pinfunction "A_3") (pintype "passive"))
      (node (ref "D6") (pin "4") (pinfunction "C_4") (pintype "passive"))
      (node (ref "J15") (pin "2") (pinfunction "2_2") (pintype "passive"))
      (node (ref "J21") (pin "1") (pinfunction "1_1") (pintype "passive"))
    )
    (net (code "76") (name "M0") (class "Default")
      (node (ref "IC1") (pin "60") (pinfunction "(A15)PC7_60") (pintype "bidirectional"))
      (node (ref "J7") (pin "M0") (pinfunction "15_M0") (pintype "passive"))
    )
    (net (code "77") (name "M1") (class "Default")
      (node (ref "IC1") (pin "59") (pinfunction "(A14)PC6_59") (pintype "bidirectional"))
      (node (ref "J7") (pin "M1") (pinfunction "14_M1") (pintype "passive"))
    )
    (net (code "78") (name "M2") (class "Default")
      (node (ref "IC1") (pin "58") (pinfunction "(A13)PC5_58") (pintype "bidirectional"))
      (node (ref "J7") (pin "M2") (pinfunction "13_M2") (pintype "passive"))
    )
    (net (code "79") (name "MISO") (class "Default")
      (node (ref "IC1") (pin "22") (pinfunction "(MISO/PCINT3)PB3_22") (pintype "bidirectional"))
      (node (ref "JP11") (pin "1") (pinfunction "1_1") (pintype "passive"))
      (node (ref "TP8") (pin "P$1") (pinfunction "1_P$1") (pintype "bidirectional"))
    )
    (net (code "80") (name "MOSI") (class "Default")
      (node (ref "IC1") (pin "21") (pinfunction "(MOSI/PCINT2)PB2_21") (pintype "bidirectional"))
      (node (ref "JP11") (pin "4") (pinfunction "4_4") (pintype "passive"))
      (node (ref "TP7") (pin "P$1") (pinfunction "1_P$1") (pintype "bidirectional"))
    )
    (net (code "81") (name "Net-(C4-Pad2)") (class "Default")
      (node (ref "C4") (pin "2") (pinfunction "2_2") (pintype "passive"))
      (node (ref "R2") (pin "1") (pinfunction "1_1") (pintype "passive"))
      (node (ref "Y1") (pin "1") (pinfunction "1_1") (pintype "passive"))
    )
    (net (code "82") (name "Net-(D7-C)") (class "Default")
      (node (ref "C33") (pin "1") (pinfunction "1_1") (pintype "passive"))
      (node (ref "C34") (pin "1") (pinfunction "1_1") (pintype "passive"))
      (node (ref "D7") (pin "2") (pinfunction "C_2") (pintype "passive"))
      (node (ref "U10") (pin "1") (pinfunction "INPUT_1") (pintype "input"))
    )
    (net (code "83") (name "Net-(D8-C)") (class "Default")
      (node (ref "C36") (pin "1") (pinfunction "1_1") (pintype "passive"))
      (node (ref "C37") (pin "1") (pinfunction "1_1") (pintype "passive"))
      (node (ref "D8") (pin "2") (pinfunction "C_2") (pintype "passive"))
      (node (ref "U11") (pin "1") (pinfunction "INPUT_1") (pintype "input"))
    )
    (net (code "84") (name "Net-(LED1-PadA)") (class "Default")
      (node (ref "LED1") (pin "A") (pinfunction "A_A") (pintype "passive"))
      (node (ref "R3") (pin "2") (pinfunction "2_2") (pintype "passive"))
    )
    (net (code "85") (name "Net-(LED2-PadA)") (class "Default")
      (node (ref "LED2") (pin "A") (pinfunction "A_A") (pintype "passive"))
      (node (ref "R4") (pin "2") (pinfunction "2_2") (pintype "passive"))
    )
    (net (code "86") (name "Net-(LED3-PadA)") (class "Default")
      (node (ref "LED3") (pin "A") (pinfunction "A_A") (pintype "passive"))
      (node (ref "R5") (pin "2") (pinfunction "2_2") (pintype "passive"))
    )
    (net (code "87") (name "Net-(LED4-PadA)") (class "Default")
      (node (ref "LED4") (pin "A") (pinfunction "A_A") (pintype "passive"))
      (node (ref "R6") (pin "2") (pinfunction "2_2") (pintype "passive"))
    )
    (net (code "88") (name "Net-(LED5-PadA)") (class "Default")
      (node (ref "LED5") (pin "A") (pinfunction "A_A") (pintype "passive"))
      (node (ref "R7") (pin "2") (pinfunction "2_2") (pintype "passive"))
    )
    (net (code "89") (name "Net-(R16-Pad2)") (class "Default")
      (node (ref "R16") (pin "2") (pinfunction "2_2") (pintype "passive"))
      (node (ref "U4") (pin "2") (pinfunction "2_2") (pintype "passive"))
    )
    (net (code "90") (name "Net-(R17-Pad2)") (class "Default")
      (node (ref "R17") (pin "2") (pinfunction "2_2") (pintype "passive"))
      (node (ref "U5") (pin "2") (pinfunction "2_2") (pintype "passive"))
    )
    (net (code "91") (name "PIVOT_CS") (class "Default")
      (node (ref "U7") (pin "13") (pinfunction "CS_13") (pintype "bidirectional"))
    )
    (net (code "92") (name "PIVOT_ENC_A") (class "Default")
      (node (ref "IC1") (pin "6") (pinfunction "(OC3B/INT4)PE4_6") (pintype "bidirectional"))
      (node (ref "J19") (pin "3") (pinfunction "3_3") (pintype "passive"))
    )
    (net (code "93") (name "PIVOT_ENC_B") (class "Default")
      (node (ref "IC1") (pin "7") (pinfunction "(OC3C/INT5)PE5_7") (pintype "bidirectional"))
      (node (ref "J19") (pin "2") (pinfunction "2_2") (pintype "passive"))
    )
    (net (code "94") (name "PIVOT_INA") (class "Default")
      (node (ref "IC1") (pin "63") (pinfunction "PJ0(RXD3/PCINT9)_63") (pintype "bidirectional"))
      (node (ref "U7") (pin "3") (pinfunction "IN_A_3") (pintype "input"))
    )
    (net (code "95") (name "PIVOT_INB") (class "Default")
      (node (ref "IC1") (pin "64") (pinfunction "PJ1(TXD3/PCINT10)_64") (pintype "bidirectional"))
      (node (ref "U7") (pin "6") (pinfunction "IN_B_6") (pintype "input"))
    )
    (net (code "96") (name "PIVOT_OUT_A") (class "Default")
      (node (ref "J11") (pin "1") (pinfunction "1_1") (pintype "passive"))
      (node (ref "U7") (pin "15") (pinfunction "OUT_A-1_15") (pintype "output"))
      (node (ref "U7") (pin "2") (pinfunction "OUT_A_2") (pintype "output"))
    )
    (net (code "97") (name "PIVOT_OUT_B") (class "Default")
      (node (ref "J11") (pin "2") (pinfunction "2_2") (pintype "passive"))
      (node (ref "U7") (pin "10") (pinfunction "OUT_B-1_10") (pintype "output"))
      (node (ref "U7") (pin "7") (pinfunction "OUT_B_7") (pintype "output"))
    )
    (net (code "98") (name "PIVOT_PWM") (class "Default")
      (node (ref "IC1") (pin "1") (pinfunction "(OC0B)PG5_1") (pintype "bidirectional"))
      (node (ref "U7") (pin "11") (pinfunction "PWM_11") (pintype "bidirectional"))
    )
    (net (code "99") (name "POWDER1") (class "Default")
      (node (ref "J6") (pin "2") (pinfunction "2_2") (pintype "passive"))
      (node (ref "U3") (pin "13") (pinfunction "OUT4-1_13") (pintype "output"))
      (node (ref "U3") (pin "14") (pinfunction "OUT4_14") (pintype "output"))
      (node (ref "U3") (pin "15") (pinfunction "OUT4-2_15") (pintype "output"))
    )
    (net (code "100") (name "POWDER1_EN") (class "Default")
      (node (ref "IC1") (pin "41") (pinfunction "PL6_41") (pintype "bidirectional"))
      (node (ref "U3") (pin "9") (pinfunction "IN4_9") (pintype "input"))
    )
    (net (code "101") (name "P_STAT1") (class "Default")
      (node (ref "U3") (pin "10") (pinfunction "STAT4_10") (pintype "bidirectional"))
    )
    (net (code "102") (name "RELAY-") (class "Default")
      (node (ref "K1") (pin "A1") (pinfunction "A1_A1") (pintype "passive"))
      (node (ref "Q1") (pin "D") (pinfunction "D_D") (pintype "passive"))
    )
    (net (code "103") (name "RESET") (class "Default")
      (node (ref "C1") (pin "1") (pinfunction "1_1") (pintype "passive"))
      (node (ref "IC1") (pin "30") (pinfunction "RESET_30") (pintype "input"))
      (node (ref "JP11") (pin "5") (pinfunction "5_5") (pintype "passive"))
      (node (ref "R1") (pin "1") (pinfunction "1_1") (pintype "passive"))
      (node (ref "S1") (pin "1") (pinfunction "1_1") (pintype "passive"))
      (node (ref "S1") (pin "2") (pinfunction "2_2") (pintype "passive"))
    )
    (net (code "104") (name "SCK") (class "Default")
      (node (ref "IC1") (pin "20") (pinfunction "(SCK/PCINT1)PB1_20") (pintype "bidirectional"))
      (node (ref "JP11") (pin "3") (pinfunction "3_3") (pintype "passive"))
      (node (ref "TP9") (pin "P$1") (pinfunction "1_P$1") (pintype "bidirectional"))
    )
    (net (code "105") (name "SCL") (class "Default")
      (node (ref "IC1") (pin "43") (pinfunction "(SCL/INT0)PD0_43") (pintype "bidirectional"))
      (node (ref "J1") (pin "1") (pinfunction "1_1") (pintype "passive"))
      (node (ref "R14") (pin "1") (pinfunction "1_1") (pintype "passive"))
      (node (ref "TP14") (pin "P$1") (pinfunction "1_P$1") (pintype "bidirectional"))
      (node (ref "U1") (pin "4") (pinfunction "SCL_4") (pintype "bidirectional"))
    )
    (net (code "106") (name "SDA") (class "Default")
      (node (ref "IC1") (pin "44") (pinfunction "(SDA/INT1)PD1_44") (pintype "bidirectional"))
      (node (ref "J1") (pin "2") (pinfunction "2_2") (pintype "passive"))
      (node (ref "R15") (pin "1") (pinfunction "1_1") (pintype "passive"))
      (node (ref "TP15") (pin "P$1") (pinfunction "1_P$1") (pintype "bidirectional"))
      (node (ref "U1") (pin "3") (pinfunction "SDA_3") (pintype "bidirectional"))
    )
    (net (code "107") (name "STEP") (class "Default")
      (node (ref "IC1") (pin "26") (pinfunction "(OC0A/OC1C/PCINT7)PB7_26") (pintype "bidirectional"))
      (node (ref "J7") (pin "STEP") (pinfunction "10_STEP") (pintype "passive"))
    )
    (net (code "108") (name "THERMISTOR0") (class "Default")
      (node (ref "C29") (pin "1") (pinfunction "1_1") (pintype "passive"))
      (node (ref "IC1") (pin "97") (pinfunction "(ADC0)PF0_97") (pintype "bidirectional"))
      (node (ref "J19") (pin "5") (pinfunction "5_5") (pintype "passive"))
      (node (ref "R29") (pin "1") (pinfunction "1_1") (pintype "passive"))
    )
    (net (code "109") (name "THERMISTOR1") (class "Default")
      (node (ref "C28") (pin "1") (pinfunction "1_1") (pintype "passive"))
      (node (ref "IC1") (pin "96") (pinfunction "(ADC1)PF1_96") (pintype "bidirectional"))
      (node (ref "J20") (pin "2") (pinfunction "2_2") (pintype "passive"))
      (node (ref "R28") (pin "1") (pinfunction "1_1") (pintype "passive"))
    )
    (net (code "110") (name "V-5_LOAD") (class "Default")
      (node (ref "C19") (pin "1") (pinfunction "1_1") (pintype "passive"))
      (node (ref "C23") (pin "1") (pinfunction "1_1") (pintype "passive"))
      (node (ref "C38") (pin "1") (pinfunction "1_1") (pintype "passive"))
      (node (ref "J7") (pin "/RESET") (pinfunction "12_/RESET") (pintype "passive"))
      (node (ref "J7") (pin "/SLEEP") (pinfunction "11_/SLEEP") (pintype "passive"))
      (node (ref "JP20") (pin "1") (pinfunction "1_1") (pintype "passive"))
      (node (ref "Q2") (pin "G") (pinfunction "G_G") (pintype "passive"))
      (node (ref "R18") (pin "2") (pinfunction "2_2") (pintype "passive"))
      (node (ref "TP19") (pin "P$1") (pinfunction "1_P$1") (pintype "bidirectional"))
      (node (ref "U11") (pin "3") (pinfunction "OUTPUT_3") (pintype "output"))
      (node (ref "U6") (pin "3") (pinfunction "V+_3") (pintype "power_in"))
      (node (ref "U8") (pin "3") (pinfunction "V+_3") (pintype "power_in"))
    )
    (net (code "111") (name "V-12V_PROT") (class "Default")
      (node (ref "C16") (pin "+") (pinfunction "+_+") (pintype "passive"))
      (node (ref "C17") (pin "+") (pinfunction "+_+") (pintype "passive"))
      (node (ref "C21") (pin "1") (pinfunction "1_1") (pintype "passive"))
      (node (ref "C22") (pin "+") (pinfunction "+_+") (pintype "passive"))
      (node (ref "C25") (pin "1") (pinfunction "1_1") (pintype "passive"))
      (node (ref "C26") (pin "+") (pinfunction "+_+") (pintype "passive"))
      (node (ref "Q6") (pin "D") (pinfunction "D_D") (pintype "bidirectional"))
      (node (ref "TP17") (pin "P$1") (pinfunction "1_P$1") (pintype "bidirectional"))
      (node (ref "U2") (pin "1") (pinfunction "VCC-1_1") (pintype "power_in"))
      (node (ref "U2") (pin "12") (pinfunction "VCC_12") (pintype "power_in"))
      (node (ref "U2") (pin "25") (pinfunction "VCC-2_25") (pintype "power_in"))
      (node (ref "U3") (pin "1") (pinfunction "VCC-1_1") (pintype "power_in"))
      (node (ref "U3") (pin "12") (pinfunction "VCC_12") (pintype "power_in"))
      (node (ref "U3") (pin "25") (pinfunction "VCC-2_25") (pintype "power_in"))
      (node (ref "U4") (pin "4") (pinfunction "4_4") (pintype "passive"))
      (node (ref "U5") (pin "4") (pinfunction "4_4") (pintype "passive"))
      (node (ref "U7") (pin "12") (pinfunction "VCC-2_12") (pintype "power_in"))
      (node (ref "U7") (pin "4") (pinfunction "VCC_4") (pintype "power_in"))
      (node (ref "U7") (pin "5") (pinfunction "VCC-1_5") (pintype "power_in"))
      (node (ref "U9") (pin "12") (pinfunction "VCC-2_12") (pintype "power_in"))
      (node (ref "U9") (pin "4") (pinfunction "VCC_4") (pintype "power_in"))
      (node (ref "U9") (pin "5") (pinfunction "VCC-1_5") (pintype "power_in"))
    )
    (net (code "112") (name "V-HEATPUMP") (class "Default")
      (node (ref "J15") (pin "1") (pinfunction "1_1") (pintype "passive"))
      (node (ref "K1") (pin "COM") (pinfunction "COM_COM") (pintype "passive"))
    )
    (net (code "113") (name "V-HVDC") (class "Default")
      (node (ref "C30") (pin "+") (pinfunction "+_+") (pintype "passive"))
      (node (ref "C31") (pin "+") (pinfunction "+_+") (pintype "passive"))
      (node (ref "C32") (pin "+") (pinfunction "+_+") (pintype "passive"))
      (node (ref "D3") (pin "4") (pinfunction "C_4") (pintype "passive"))
      (node (ref "D5") (pin "4") (pinfunction "C_4") (pintype "passive"))
      (node (ref "F1") (pin "1") (pinfunction "1_1") (pintype "passive"))
      (node (ref "F2") (pin "1") (pinfunction "1_1") (pintype "passive"))
    )
    (net (code "114") (name "V-STEPPER") (class "Default")
      (node (ref "C18") (pin "+") (pinfunction "+_+") (pintype "passive"))
      (node (ref "J7") (pin "V-STEPPER") (pinfunction "1_V-STEPPER") (pintype "passive"))
      (node (ref "J8") (pin "6") (pinfunction "6_6") (pintype "passive"))
      (node (ref "JP20") (pin "2") (pinfunction "2_2") (pintype "passive"))
      (node (ref "TP16") (pin "P$1") (pinfunction "1_P$1") (pintype "bidirectional"))
    )
    (net (code "115") (name "XTAL1") (class "Default")
      (node (ref "C5") (pin "2") (pinfunction "2_2") (pintype "passive"))
      (node (ref "IC1") (pin "34") (pinfunction "XTAL1_34") (pintype "input"))
      (node (ref "Y1") (pin "2") (pinfunction "2_2") (pintype "passive"))
    )
    (net (code "116") (name "XTAL2") (class "Default")
      (node (ref "IC1") (pin "33") (pinfunction "XTAL2_33") (pintype "output"))
      (node (ref "R2") (pin "2") (pinfunction "2_2") (pintype "passive"))
    )
    (net (code "117") (name "unconnected-(IC1-(A8)PC0-Pad53)") (class "Default")
      (node (ref "IC1") (pin "53") (pinfunction "(A8)PC0_53") (pintype "bidirectional"))
    )
    (net (code "118") (name "unconnected-(IC1-(A11)PC3-Pad56)") (class "Default")
      (node (ref "IC1") (pin "56") (pinfunction "(A11)PC3_56") (pintype "bidirectional"))
    )
    (net (code "119") (name "unconnected-(IC1-(AD4)PA4-Pad74)") (class "Default")
      (node (ref "IC1") (pin "74") (pinfunction "(AD4)PA4_74") (pintype "bidirectional"))
    )
    (net (code "120") (name "unconnected-(IC1-(AD5)PA5-Pad73)") (class "Default")
      (node (ref "IC1") (pin "73") (pinfunction "(AD5)PA5_73") (pintype "bidirectional"))
    )
    (net (code "121") (name "unconnected-(IC1-(AD6)PA6-Pad72)") (class "Default")
      (node (ref "IC1") (pin "72") (pinfunction "(AD6)PA6_72") (pintype "bidirectional"))
    )
    (net (code "122") (name "unconnected-(IC1-(AD7)PA7-Pad71)") (class "Default")
      (node (ref "IC1") (pin "71") (pinfunction "(AD7)PA7_71") (pintype "bidirectional"))
    )
    (net (code "123") (name "unconnected-(IC1-(ADC3)PF3-Pad94)") (class "Default")
      (node (ref "IC1") (pin "94") (pinfunction "(ADC3)PF3_94") (pintype "bidirectional"))
    )
    (net (code "124") (name "unconnected-(IC1-(CLKO{slash}ICP3{slash}INT7)PE7-Pad9)") (class "Default")
      (node (ref "IC1") (pin "9") (pinfunction "(CLKO/ICP3/INT7)PE7_9") (pintype "bidirectional"))
    )
    (net (code "125") (name "unconnected-(IC1-(ICP1)PD4-Pad47)") (class "Default")
      (node (ref "IC1") (pin "47") (pinfunction "(ICP1)PD4_47") (pintype "bidirectional"))
    )
    (net (code "126") (name "unconnected-(IC1-(OC1A{slash}PCINT5)PB5-Pad24)") (class "Default")
      (node (ref "IC1") (pin "24") (pinfunction "(OC1A/PCINT5)PB5_24") (pintype "bidirectional"))
    )
    (net (code "127") (name "unconnected-(IC1-(OC2A{slash}PCINT4)PB4-Pad23)") (class "Default")
      (node (ref "IC1") (pin "23") (pinfunction "(OC2A/PCINT4)PB4_23") (pintype "bidirectional"))
    )
    (net (code "128") (name "unconnected-(IC1-(RXD0{slash}PCIN8)PE0-Pad2)") (class "Default")
      (node (ref "IC1") (pin "2") (pinfunction "(RXD0/PCIN8)PE0_2") (pintype "bidirectional"))
    )
    (net (code "129") (name "unconnected-(IC1-(SS{slash}PCINT0)PB0-Pad19)") (class "Default")
      (node (ref "IC1") (pin "19") (pinfunction "(SS/PCINT0)PB0_19") (pintype "bidirectional"))
    )
    (net (code "130") (name "unconnected-(IC1-(T0)PD7-Pad50)") (class "Default")
      (node (ref "IC1") (pin "50") (pinfunction "(T0)PD7_50") (pintype "bidirectional"))
    )
    (net (code "131") (name "unconnected-(IC1-(T1)PD6-Pad49)") (class "Default")
      (node (ref "IC1") (pin "49") (pinfunction "(T1)PD6_49") (pintype "bidirectional"))
    )
    (net (code "132") (name "unconnected-(IC1-(T3{slash}INT6)PE6-Pad8)") (class "Default")
      (node (ref "IC1") (pin "8") (pinfunction "(T3/INT6)PE6_8") (pintype "bidirectional"))
    )
    (net (code "133") (name "unconnected-(IC1-(TOSC1)PG4-Pad29)") (class "Default")
      (node (ref "IC1") (pin "29") (pinfunction "(TOSC1)PG4_29") (pintype "bidirectional"))
    )
    (net (code "134") (name "unconnected-(IC1-(TOSC2)PG3-Pad28)") (class "Default")
      (node (ref "IC1") (pin "28") (pinfunction "(TOSC2)PG3_28") (pintype "bidirectional"))
    )
    (net (code "135") (name "unconnected-(IC1-(TXD0)PE1-Pad3)") (class "Default")
      (node (ref "IC1") (pin "3") (pinfunction "(TXD0)PE1_3") (pintype "bidirectional"))
    )
    (net (code "136") (name "unconnected-(IC1-(XCK0{slash}AIN0)PE2-Pad4)") (class "Default")
      (node (ref "IC1") (pin "4") (pinfunction "(XCK0/AIN0)PE2_4") (pintype "bidirectional"))
    )
    (net (code "137") (name "unconnected-(IC1-(XCK1)PD5-Pad48)") (class "Default")
      (node (ref "IC1") (pin "48") (pinfunction "(XCK1)PD5_48") (pintype "bidirectional"))
    )
    (net (code "138") (name "unconnected-(IC1-PH0(RXD2)-Pad12)") (class "Default")
      (node (ref "IC1") (pin "12") (pinfunction "PH0(RXD2)_12") (pintype "bidirectional"))
    )
    (net (code "139") (name "unconnected-(IC1-PH1(TXD2)-Pad13)") (class "Default")
      (node (ref "IC1") (pin "13") (pinfunction "PH1(TXD2)_13") (pintype "bidirectional"))
    )
    (net (code "140") (name "unconnected-(IC1-PH2(XCK2)-Pad14)") (class "Default")
      (node (ref "IC1") (pin "14") (pinfunction "PH2(XCK2)_14") (pintype "bidirectional"))
    )
    (net (code "141") (name "unconnected-(IC1-PH6(OC2B)-Pad18)") (class "Default")
      (node (ref "IC1") (pin "18") (pinfunction "PH6(OC2B)_18") (pintype "bidirectional"))
    )
    (net (code "142") (name "unconnected-(IC1-PH7(T4)-Pad27)") (class "Default")
      (node (ref "IC1") (pin "27") (pinfunction "PH7(T4)_27") (pintype "bidirectional"))
    )
    (net (code "143") (name "unconnected-(IC1-PJ2(XCK3{slash}PCINT11)-Pad65)") (class "Default")
      (node (ref "IC1") (pin "65") (pinfunction "PJ2(XCK3/PCINT11)_65") (pintype "bidirectional"))
    )
    (net (code "144") (name "unconnected-(IC1-PJ3(PCINT12)-Pad66)") (class "Default")
      (node (ref "IC1") (pin "66") (pinfunction "PJ3(PCINT12)_66") (pintype "bidirectional"))
    )
    (net (code "145") (name "unconnected-(IC1-PJ4(PCINT13)-Pad67)") (class "Default")
      (node (ref "IC1") (pin "67") (pinfunction "PJ4(PCINT13)_67") (pintype "bidirectional"))
    )
    (net (code "146") (name "unconnected-(IC1-PJ5(PCINT14)-Pad68)") (class "Default")
      (node (ref "IC1") (pin "68") (pinfunction "PJ5(PCINT14)_68") (pintype "bidirectional"))
    )
    (net (code "147") (name "unconnected-(IC1-PJ6(PCINT15)-Pad69)") (class "Default")
      (node (ref "IC1") (pin "69") (pinfunction "PJ6(PCINT15)_69") (pintype "bidirectional"))
    )
    (net (code "148") (name "unconnected-(IC1-PJ7-Pad79)") (class "Default")
      (node (ref "IC1") (pin "79") (pinfunction "PJ7_79") (pintype "bidirectional"))
    )
    (net (code "149") (name "unconnected-(IC1-PK0(ADC8{slash}PCINT16)-Pad89)") (class "Default")
      (node (ref "IC1") (pin "89") (pinfunction "PK0(ADC8/PCINT16)_89") (pintype "bidirectional"))
    )
    (net (code "150") (name "unconnected-(IC1-PK1(ADC9{slash}PCINT17)-Pad88)") (class "Default")
      (node (ref "IC1") (pin "88") (pinfunction "PK1(ADC9/PCINT17)_88") (pintype "bidirectional"))
    )
    (net (code "151") (name "unconnected-(IC1-PK2(ADC10{slash}PCINT18)-Pad87)") (class "Default")
      (node (ref "IC1") (pin "87") (pinfunction "PK2(ADC10/PCINT18)_87") (pintype "bidirectional"))
    )
    (net (code "152") (name "unconnected-(IC1-PK3(ADC11{slash}PCINT19)-Pad86)") (class "Default")
      (node (ref "IC1") (pin "86") (pinfunction "PK3(ADC11/PCINT19)_86") (pintype "bidirectional"))
    )
    (net (code "153") (name "unconnected-(IC1-PL7-Pad42)") (class "Default")
      (node (ref "IC1") (pin "42") (pinfunction "PL7_42") (pintype "bidirectional"))
    )
    (net (code "154") (name "unconnected-(J8-Pad1)") (class "Default")
      (node (ref "J8") (pin "1") (pinfunction "1_1") (pintype "passive"))
    )
    (net (code "155") (name "unconnected-(K1-PadNC)") (class "Default")
      (node (ref "K1") (pin "NC") (pinfunction "NC_NC") (pintype "passive"))
    )
    (net (code "156") (name "{slash}EN") (class "Default")
      (node (ref "IC1") (pin "57") (pinfunction "(A12)PC4_57") (pintype "bidirectional"))
      (node (ref "J7") (pin "/EN") (pinfunction "16_/EN") (pintype "passive"))
    )
    (net (code "157") (name "{slash}FLT") (class "Default")
      (node (ref "J7") (pin "/FLT") (pinfunction "7_/FLT") (pintype "passive"))
    )
  )
)
